# Dashboard_rev7.net
KiCad netlist of a schematic drawn in EAGLE
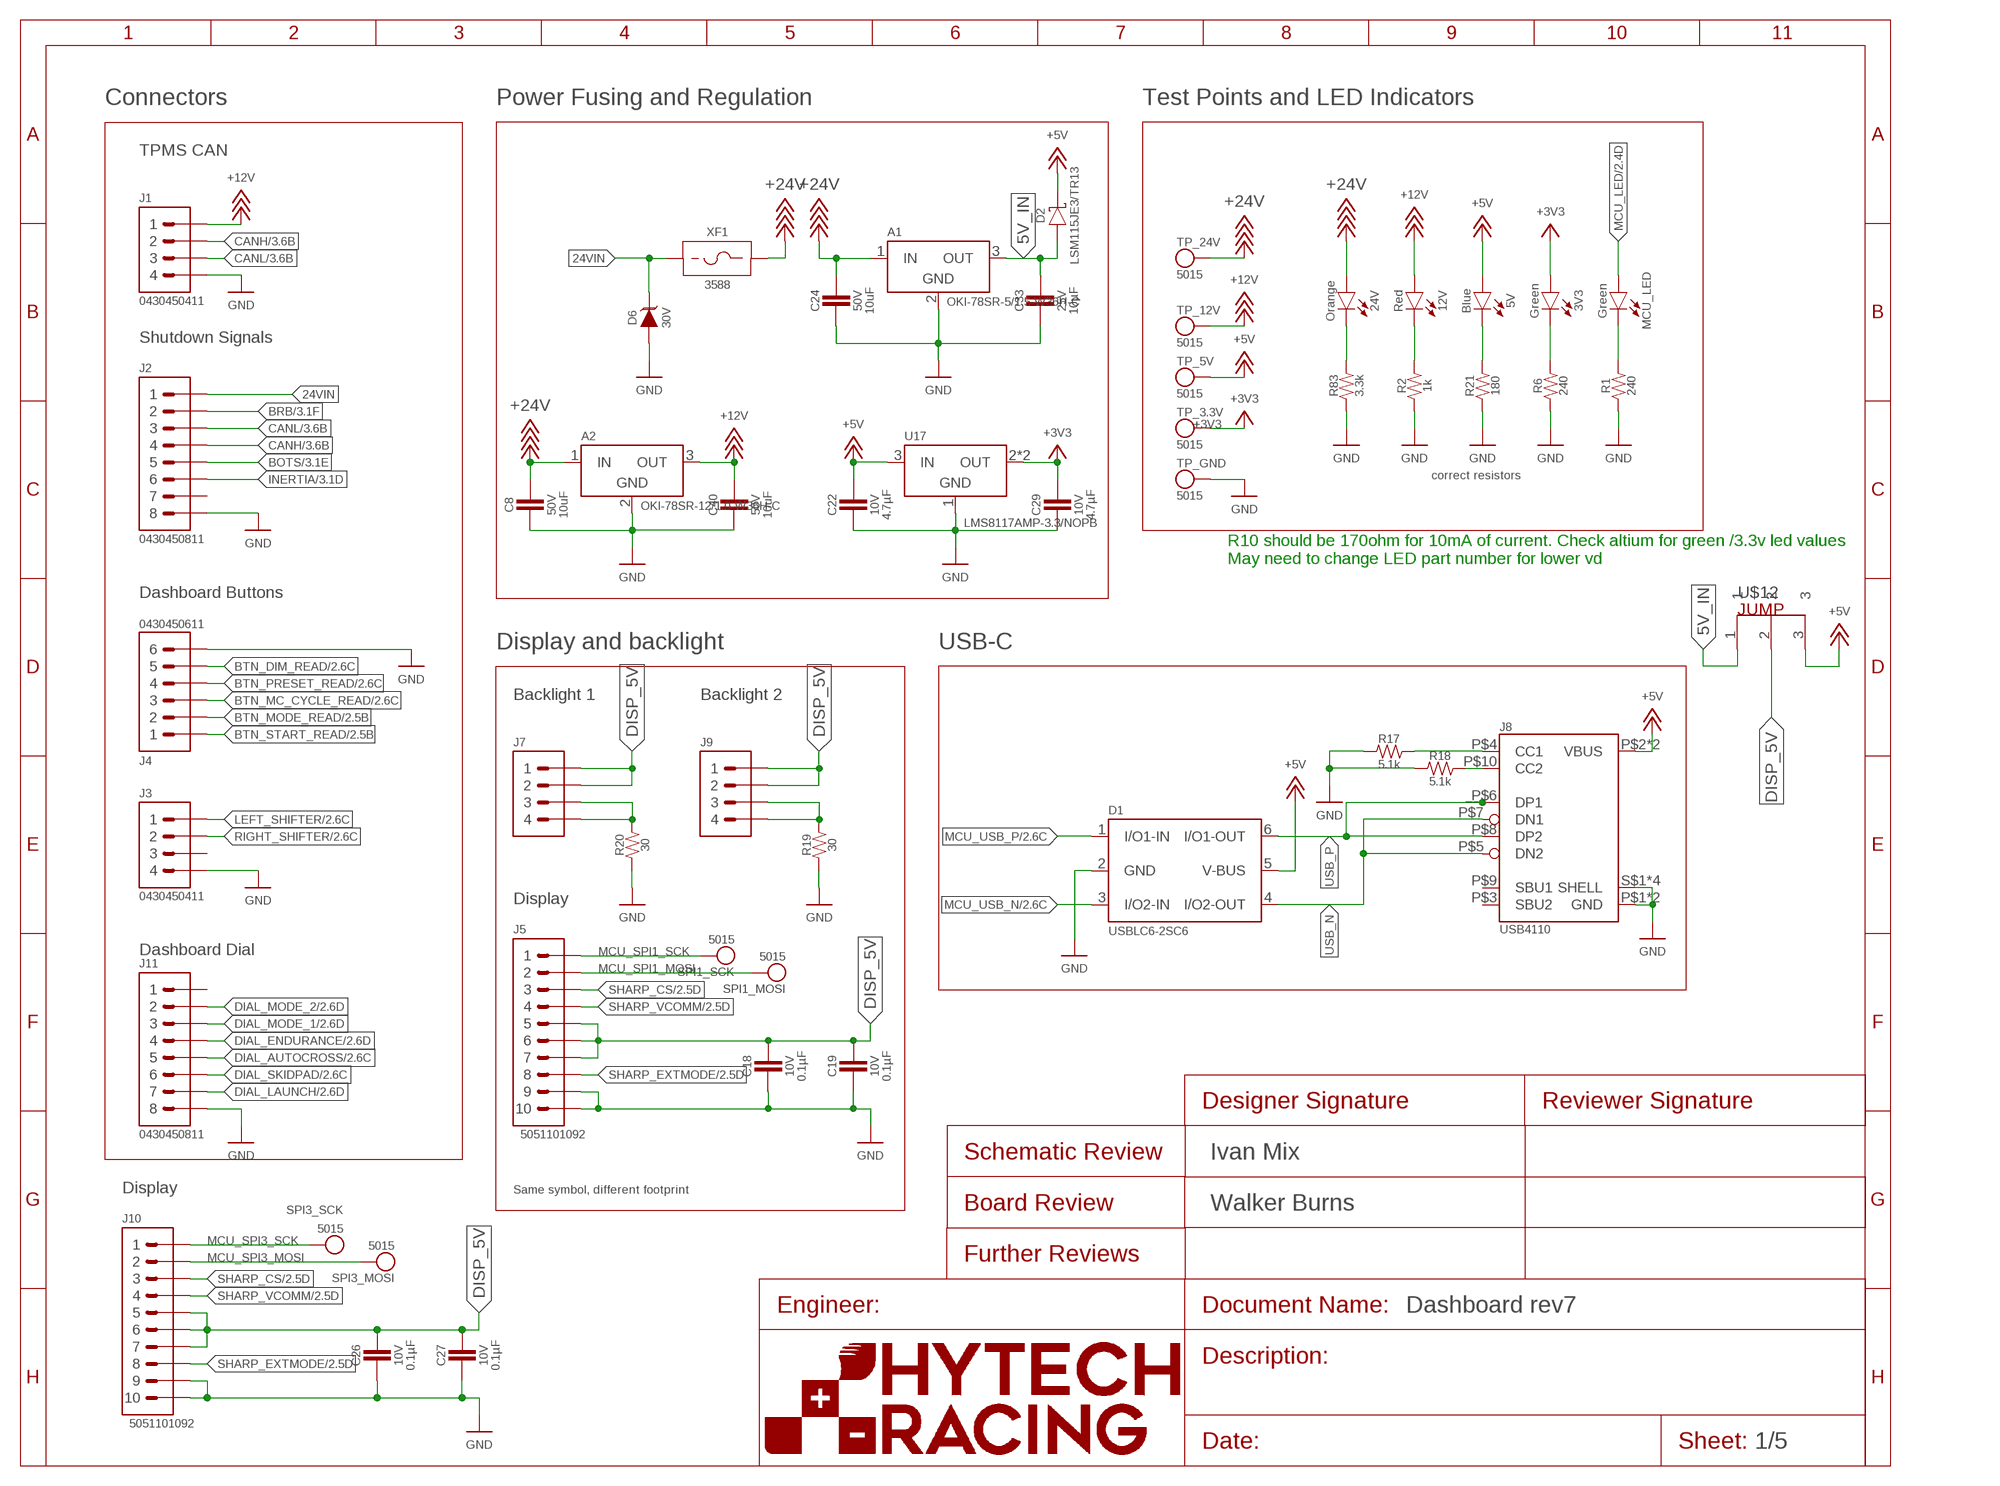
[diagram p0: schematic, sheet 1]
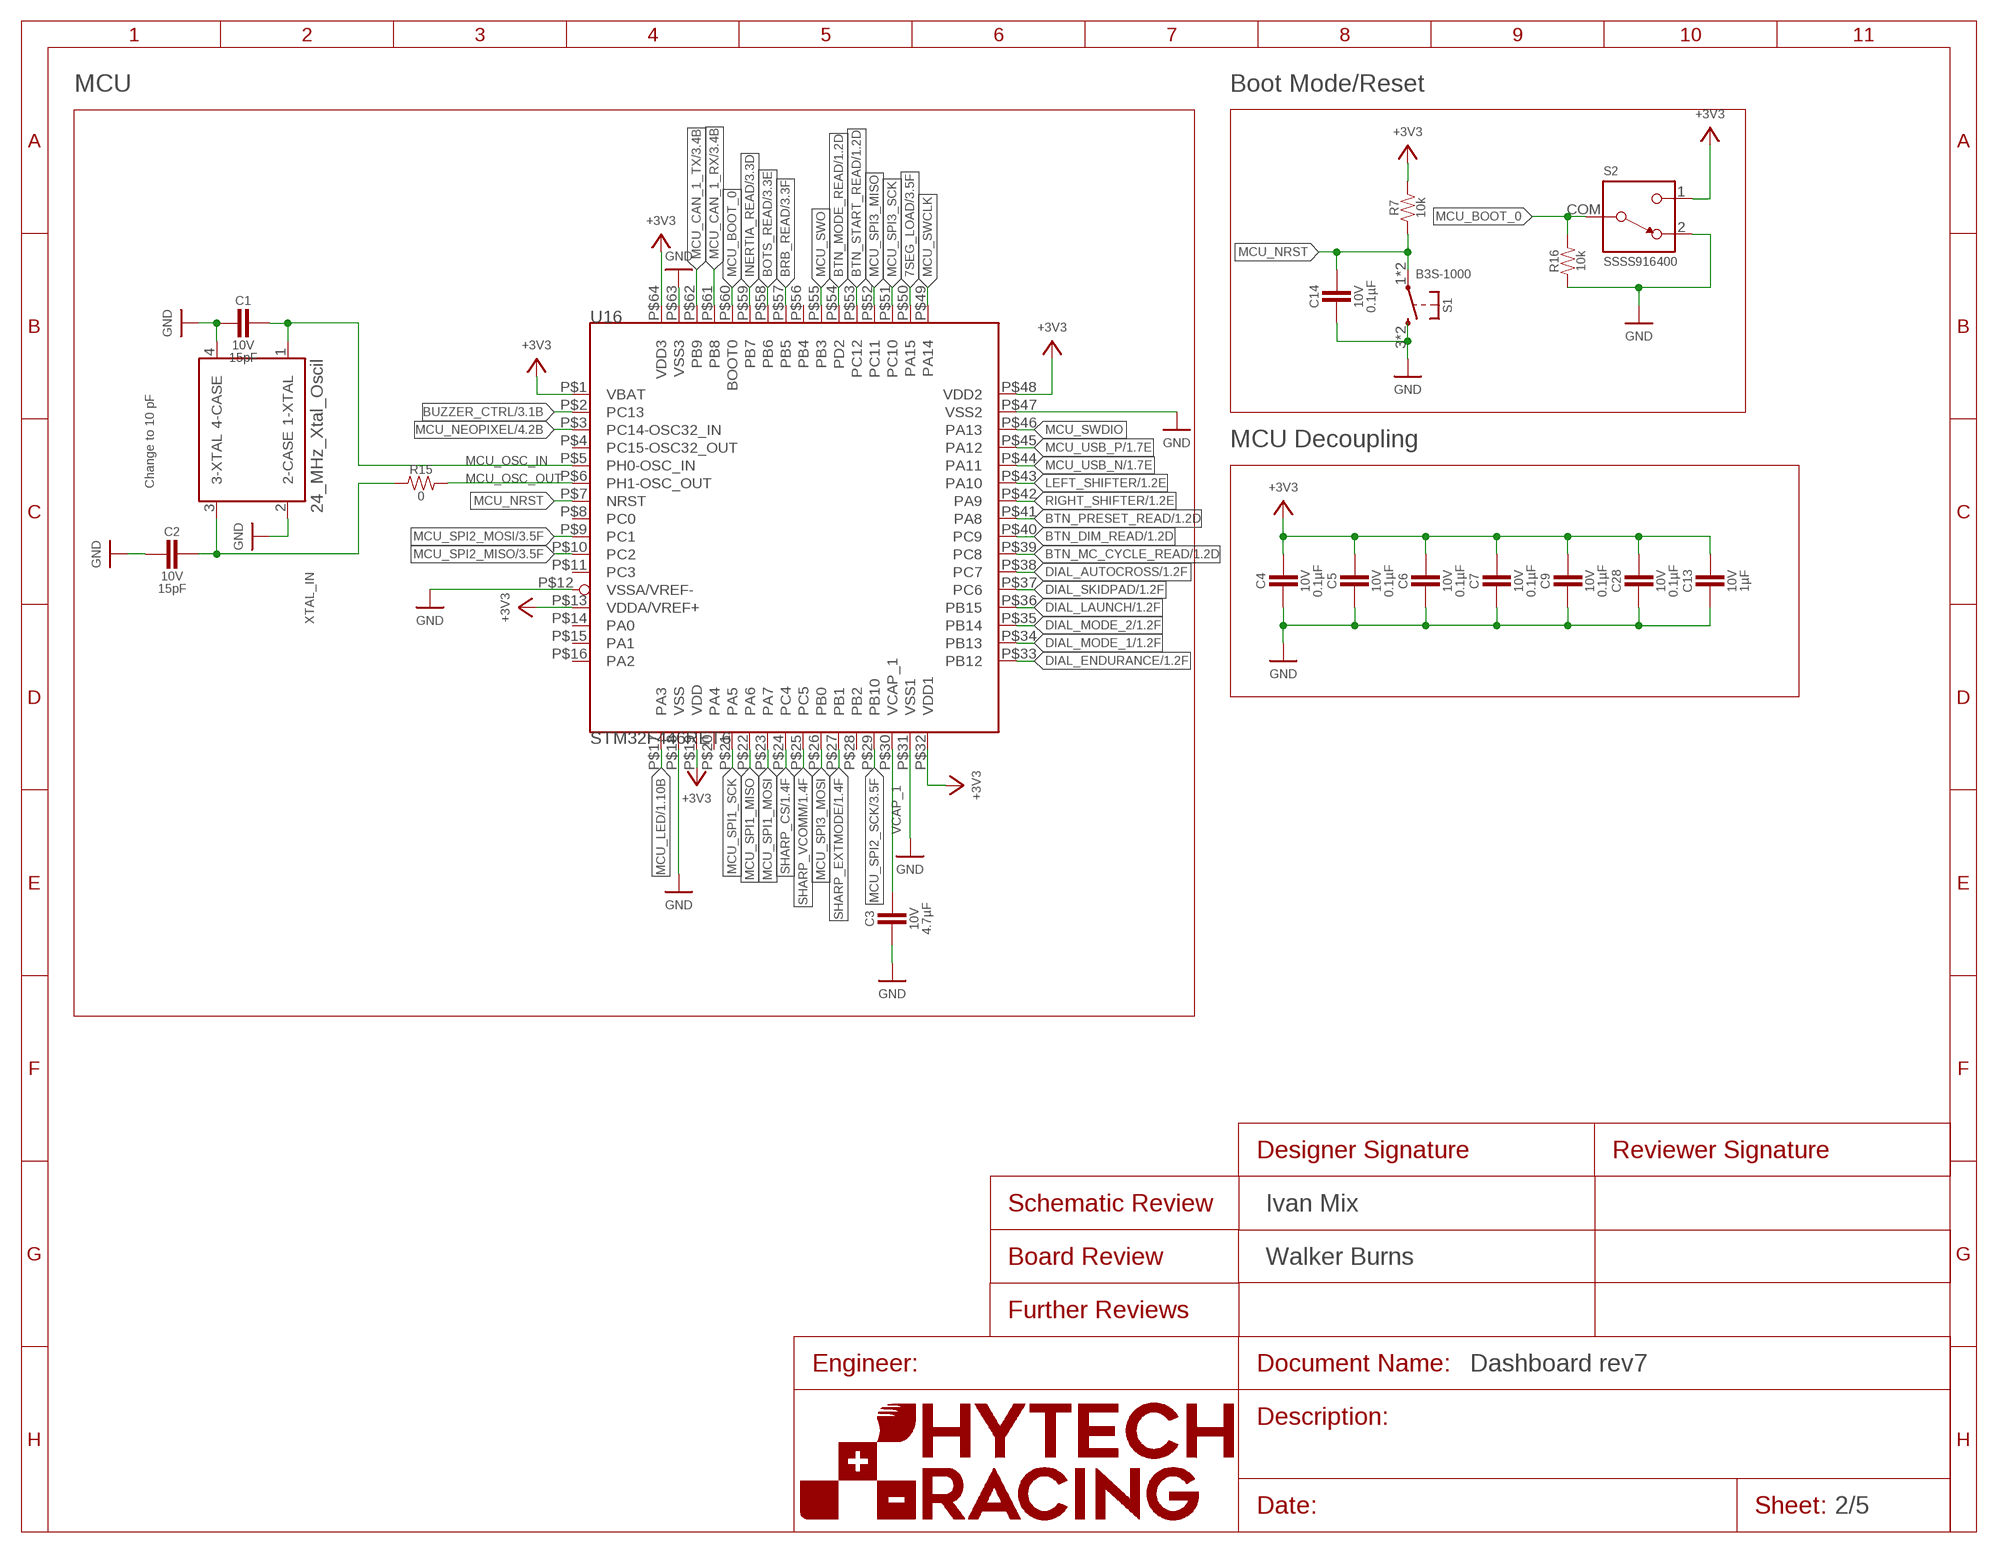
[diagram p1: schematic, sheet 2]
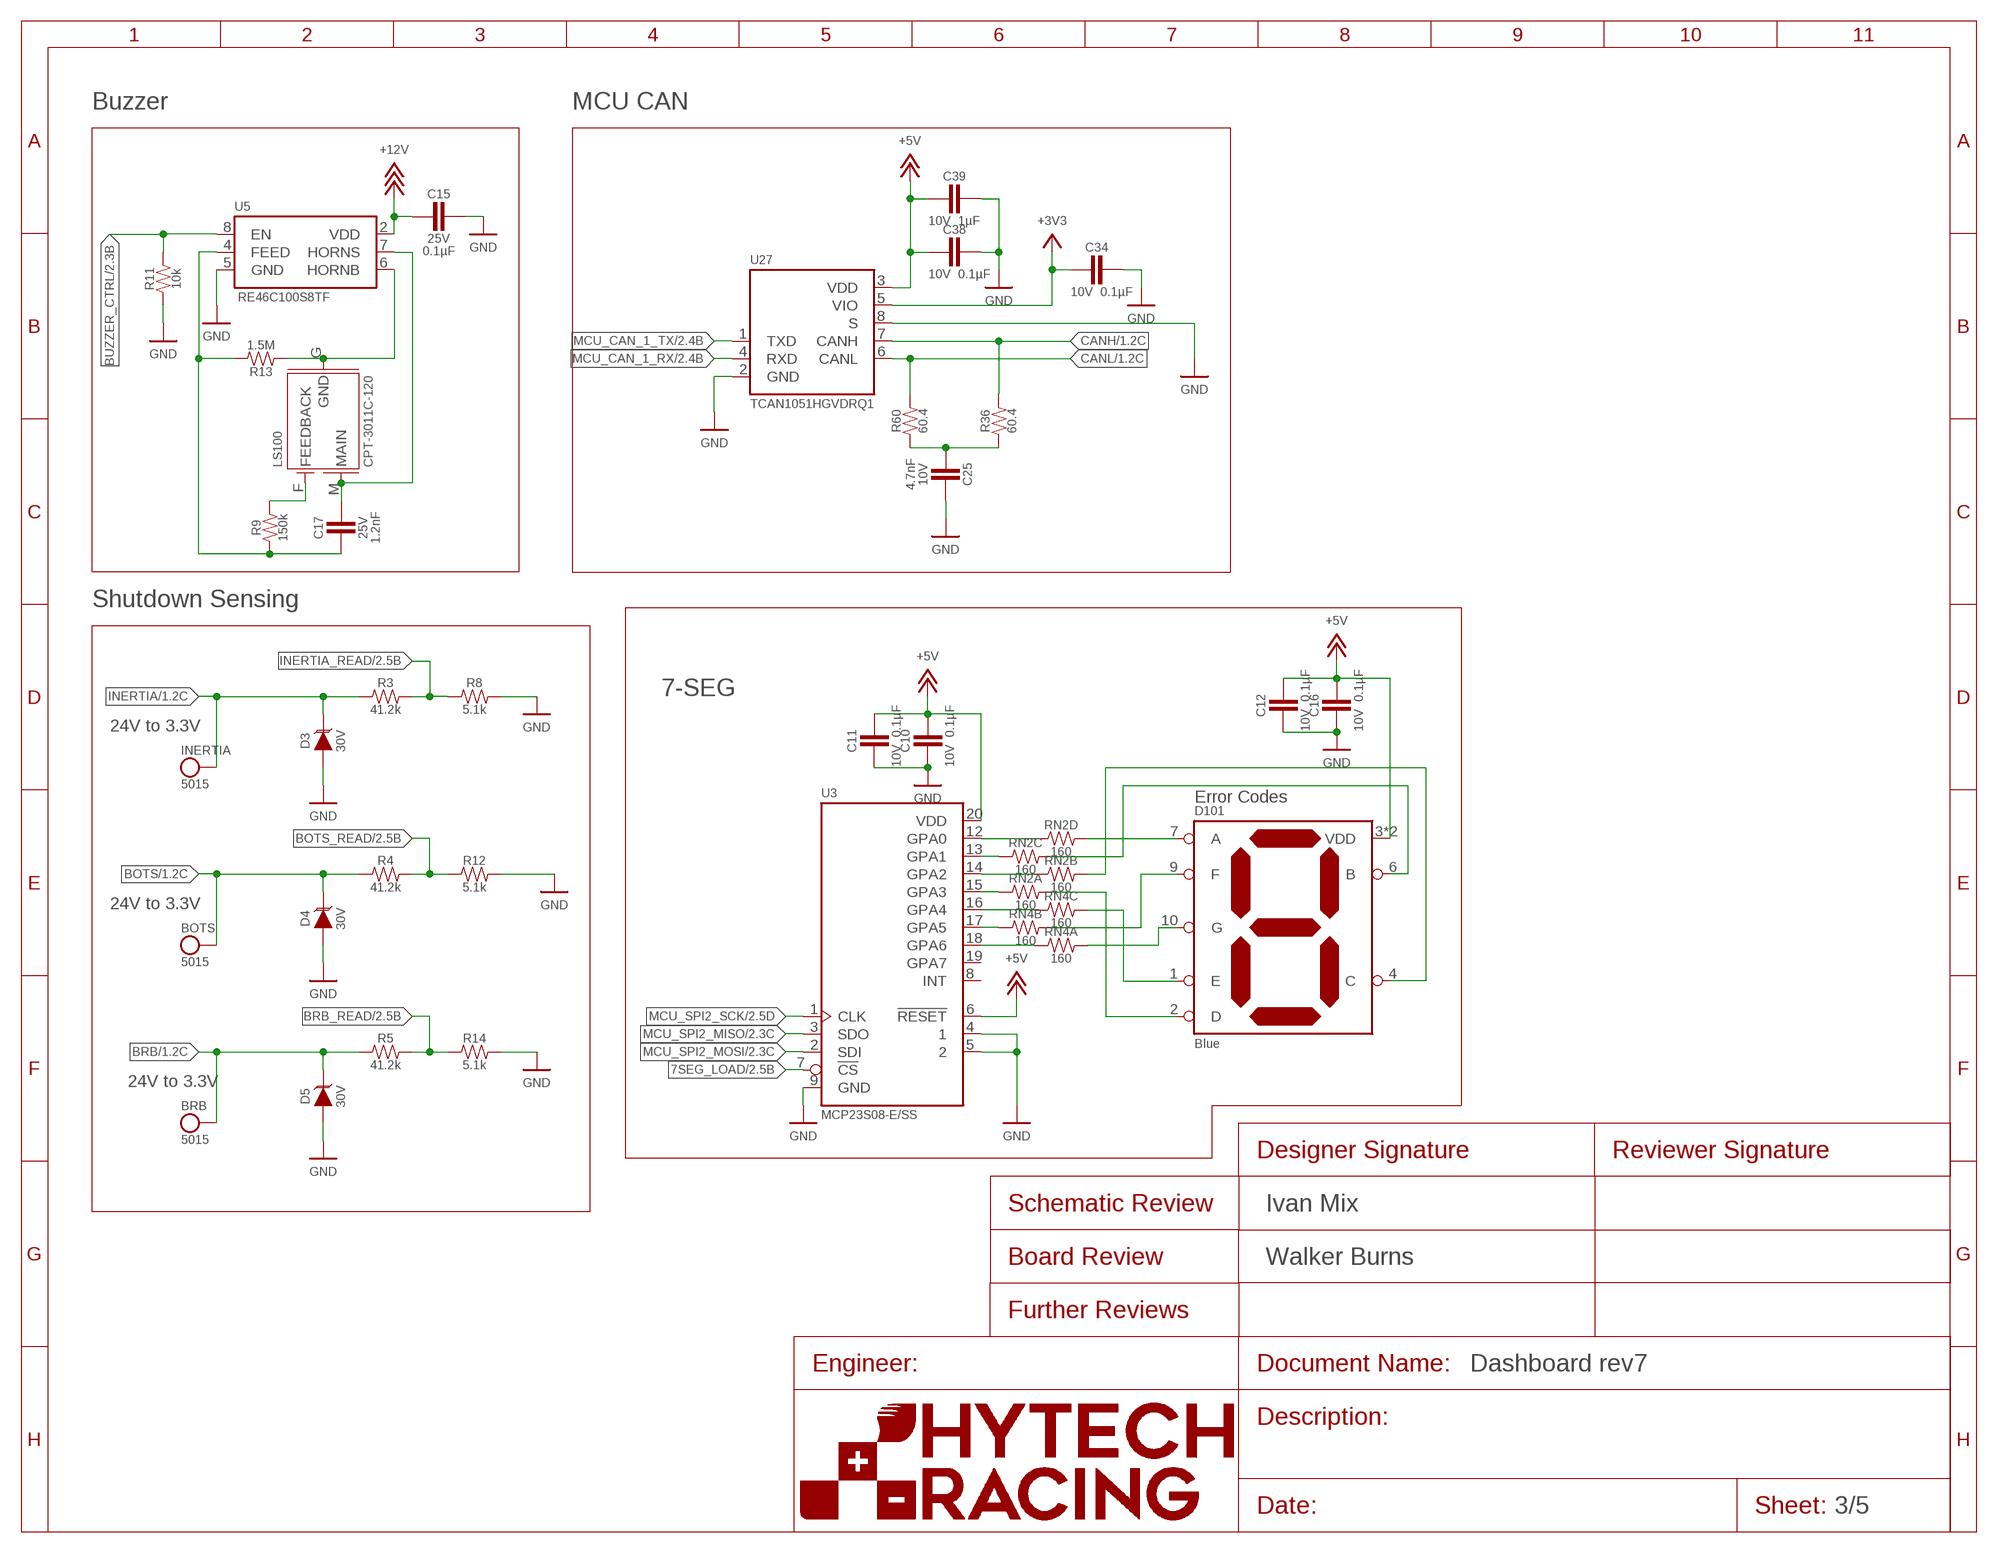
[diagram p2: schematic, sheet 3]
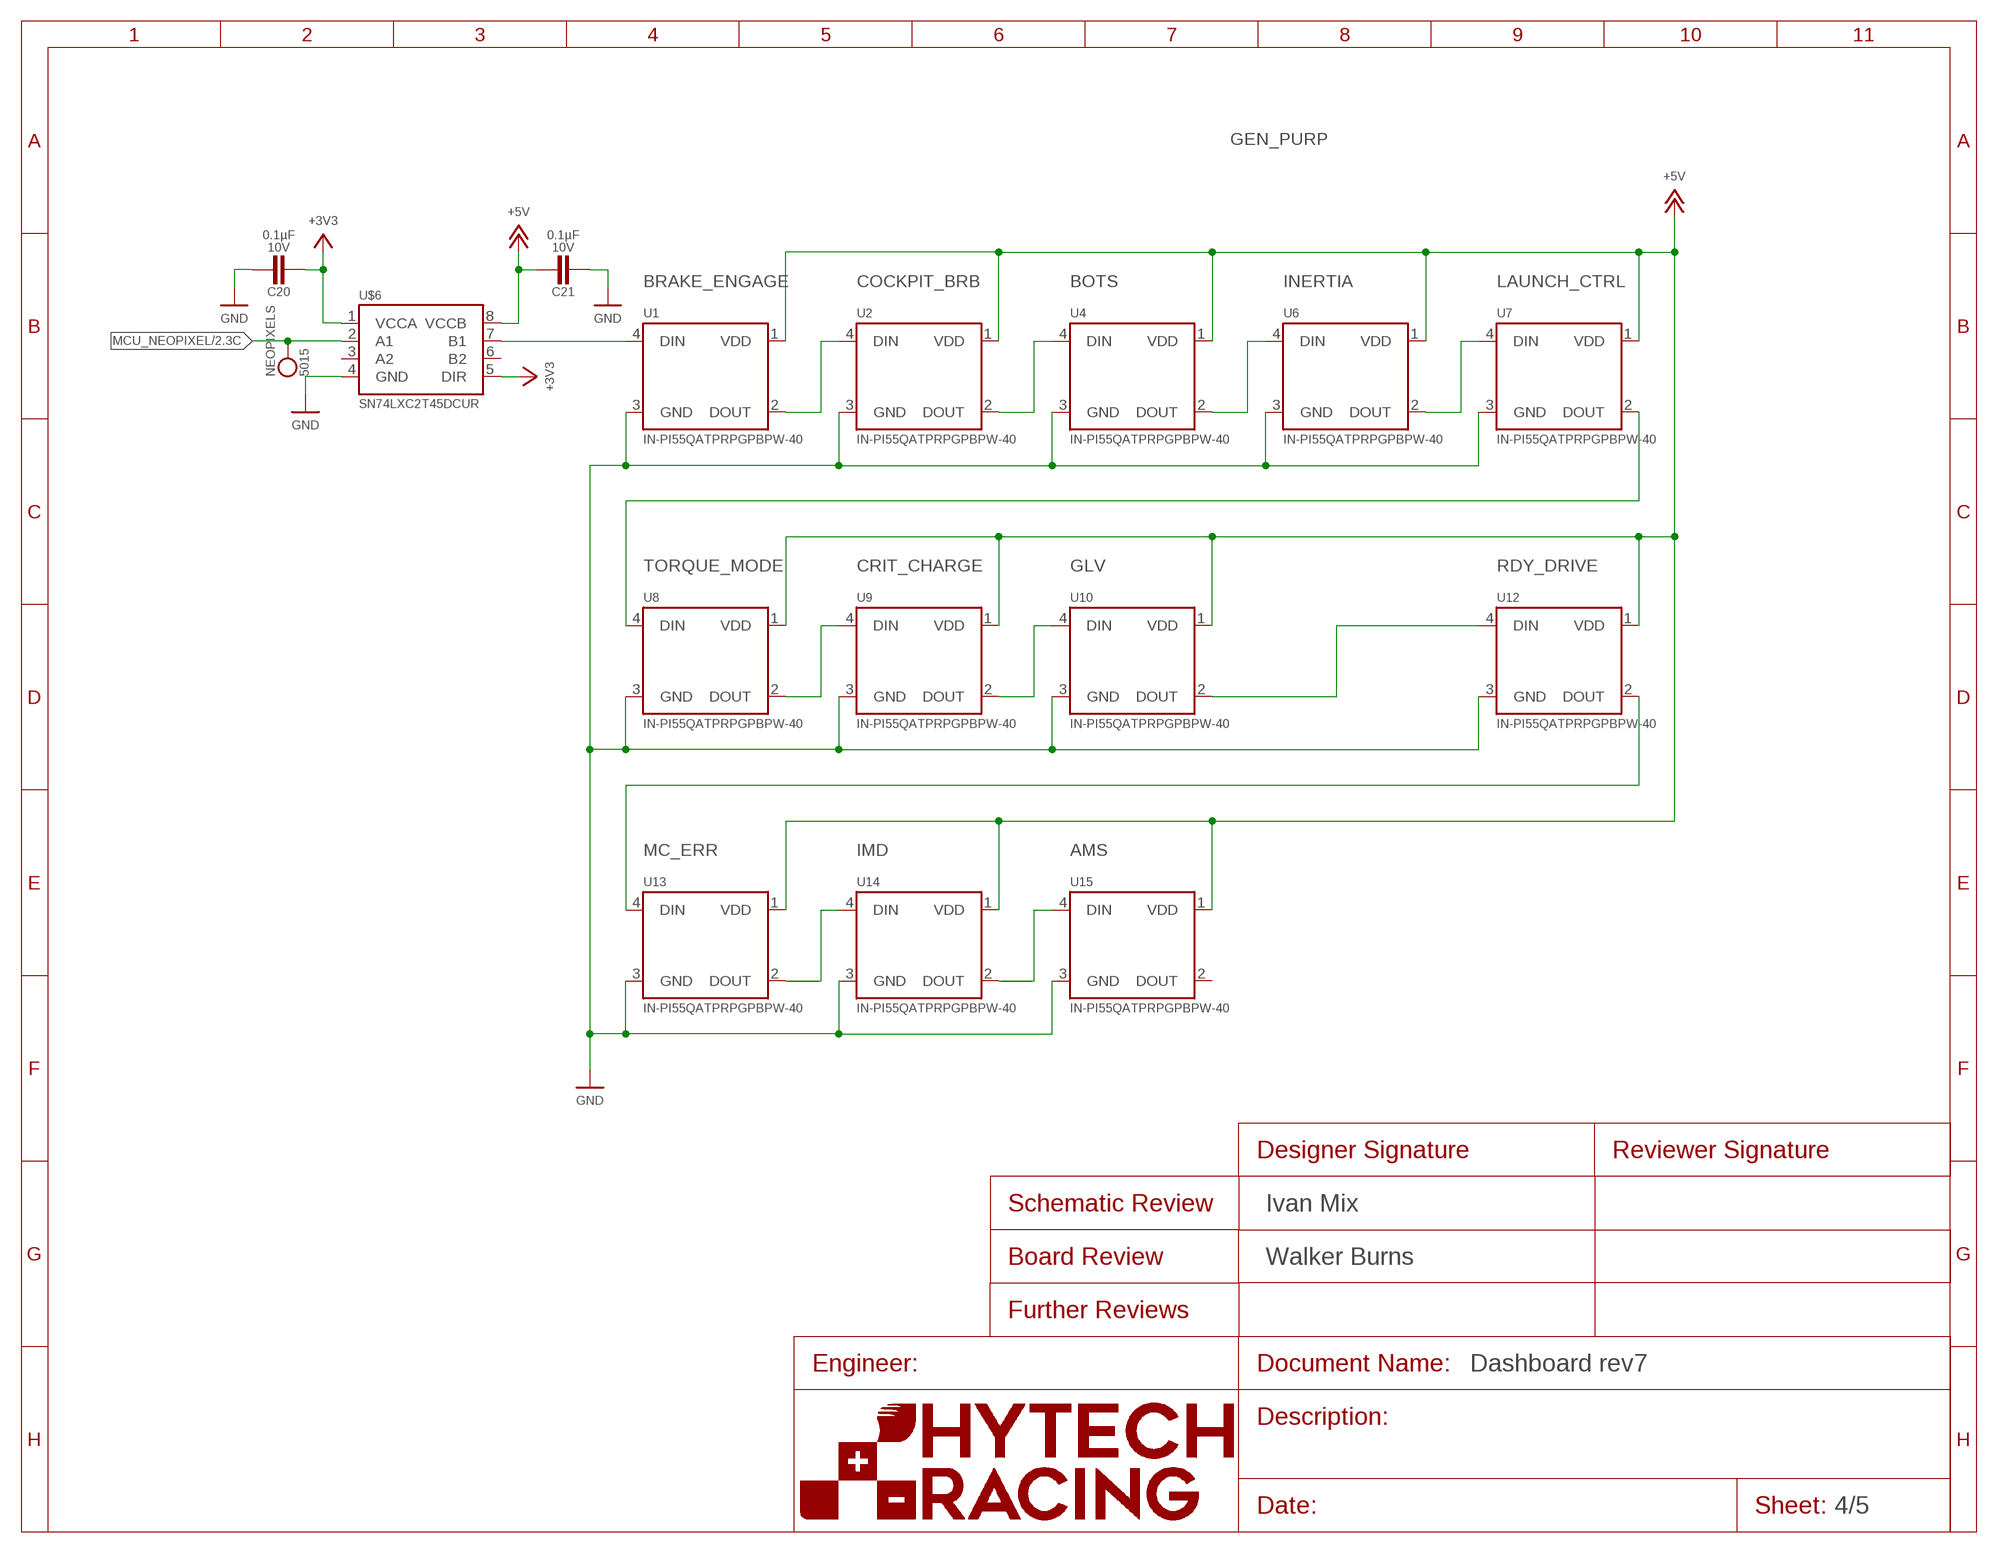
[diagram p3: schematic, sheet 4]
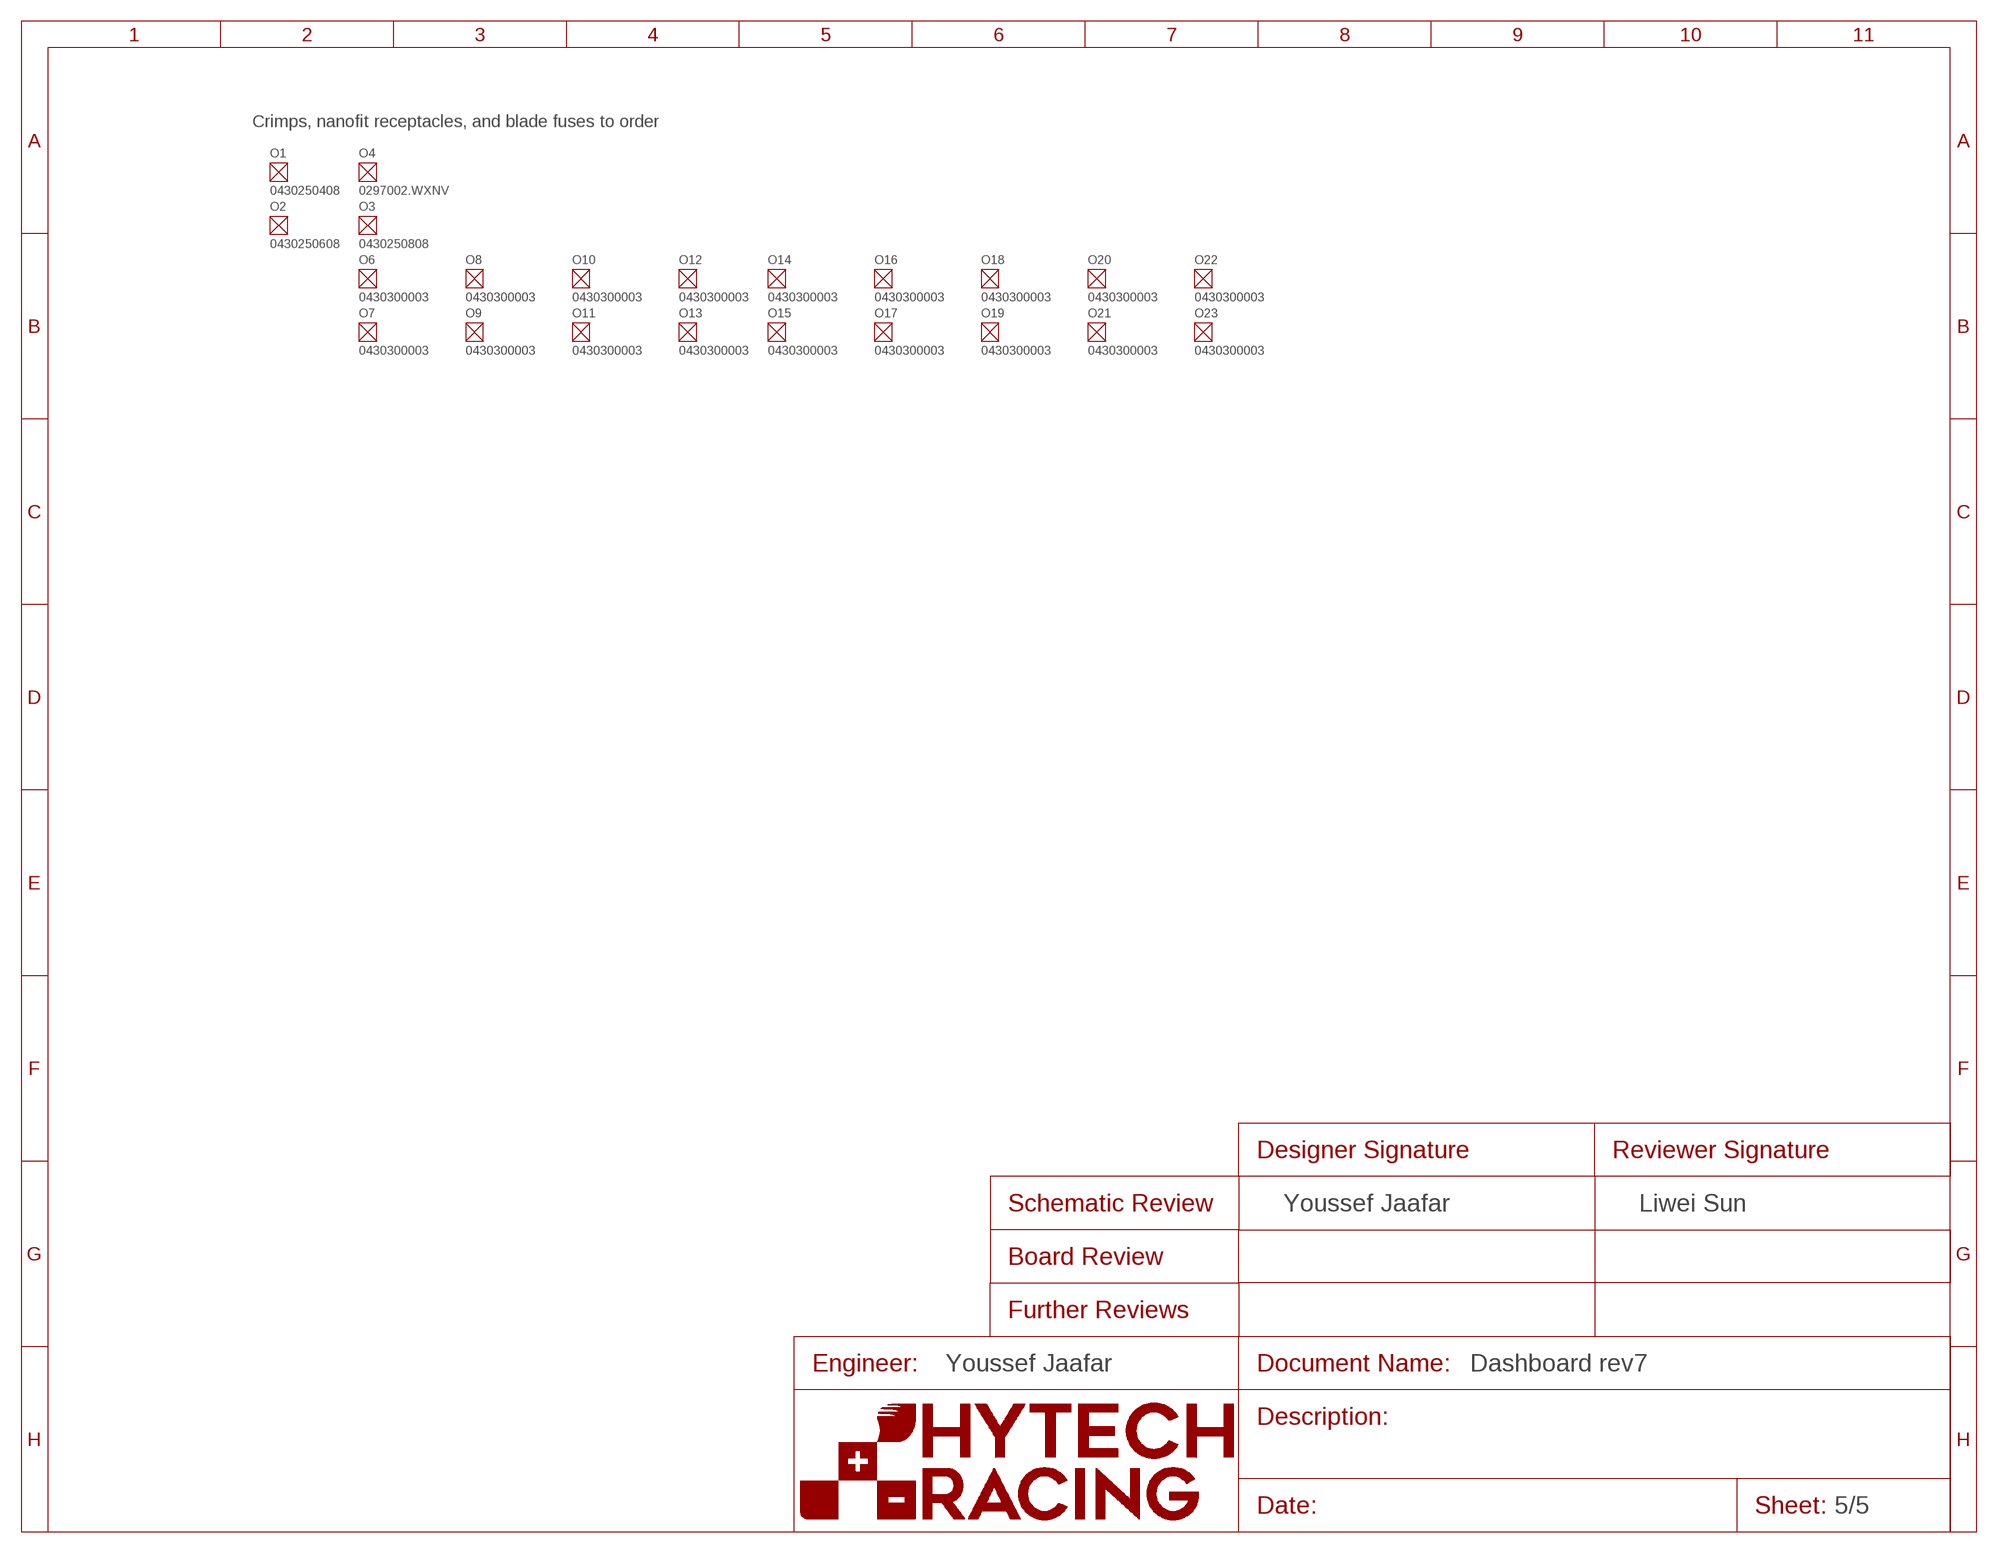
[diagram p4: schematic, sheet 5]

(export (version "E")
  (design (tool "Eeschema 10.0.6"))
  (components
    (comp (ref "C1")
      (value "CAPACITOR_0603_10V_15PF")
      (footprint "eagle-import:0603-CAP")
      (fields
        (field (name "CAPACITANCE") "15pF")
        (field (name "MANUFACTURER") "Vishay Vitramon")
        (field (name "MPN") "VJ0603A150FXQPW1BC")
        (field (name "TOLERANCE") "1%")
        (field (name "VOLTAGE") "10V")
      )
      (libsource (lib "eagle-import") (part "CAPACITOR_?_060310V_15PF"))
    )
    (comp (ref "C2")
      (value "CAPACITOR_0603_10V_15PF")
      (footprint "eagle-import:0603-CAP")
      (fields
        (field (name "CAPACITANCE") "15pF")
        (field (name "MANUFACTURER") "Vishay Vitramon")
        (field (name "MPN") "VJ0603A150FXQPW1BC")
        (field (name "TOLERANCE") "1%")
        (field (name "VOLTAGE") "10V")
      )
      (libsource (lib "eagle-import") (part "CAPACITOR_?_060310V_15PF"))
    )
    (comp (ref "C3")
      (value "CAPACITOR_0603_10V_4.7UF")
      (footprint "eagle-import:0603-CAP")
      (fields
        (field (name "CAPACITANCE") "4.7µF")
        (field (name "MANUFACTURER") "Samsung Electro-Mechanics")
        (field (name "MPN") "CL10A475KP8NNNC")
        (field (name "TOLERANCE") "10%")
        (field (name "VOLTAGE") "10V")
      )
      (libsource (lib "eagle-import") (part "CAPACITOR_?_060310V_4.7UF"))
    )
    (comp (ref "C4")
      (value "CAPACITOR_0603_10V_0.1UF")
      (footprint "eagle-import:0603-CAP")
      (fields
        (field (name "CAPACITANCE") "0.1µF")
        (field (name "MANUFACTURER") "Vishay Vitramon")
        (field (name "MPN") "VJ0603Y104JXQPW1BC")
        (field (name "TOLERANCE") "5%")
        (field (name "VOLTAGE") "10V")
      )
      (libsource (lib "eagle-import") (part "CAPACITOR_?_060310V_0.1UF"))
    )
    (comp (ref "C5")
      (value "CAPACITOR_0603_10V_0.1UF")
      (footprint "eagle-import:0603-CAP")
      (fields
        (field (name "CAPACITANCE") "0.1µF")
        (field (name "MANUFACTURER") "Vishay Vitramon")
        (field (name "MPN") "VJ0603Y104JXQPW1BC")
        (field (name "TOLERANCE") "5%")
        (field (name "VOLTAGE") "10V")
      )
      (libsource (lib "eagle-import") (part "CAPACITOR_?_060310V_0.1UF"))
    )
    (comp (ref "C6")
      (value "CAPACITOR_0603_10V_0.1UF")
      (footprint "eagle-import:0603-CAP")
      (fields
        (field (name "CAPACITANCE") "0.1µF")
        (field (name "MANUFACTURER") "Vishay Vitramon")
        (field (name "MPN") "VJ0603Y104JXQPW1BC")
        (field (name "TOLERANCE") "5%")
        (field (name "VOLTAGE") "10V")
      )
      (libsource (lib "eagle-import") (part "CAPACITOR_?_060310V_0.1UF"))
    )
    (comp (ref "C7")
      (value "CAPACITOR_0603_10V_0.1UF")
      (footprint "eagle-import:0603-CAP")
      (fields
        (field (name "CAPACITANCE") "0.1µF")
        (field (name "MANUFACTURER") "Vishay Vitramon")
        (field (name "MPN") "VJ0603Y104JXQPW1BC")
        (field (name "TOLERANCE") "5%")
        (field (name "VOLTAGE") "10V")
      )
      (libsource (lib "eagle-import") (part "CAPACITOR_?_060310V_0.1UF"))
    )
    (comp (ref "C9")
      (value "CAPACITOR_0603_10V_0.1UF")
      (footprint "eagle-import:0603-CAP")
      (fields
        (field (name "CAPACITANCE") "0.1µF")
        (field (name "MANUFACTURER") "Vishay Vitramon")
        (field (name "MPN") "VJ0603Y104JXQPW1BC")
        (field (name "TOLERANCE") "5%")
        (field (name "VOLTAGE") "10V")
      )
      (libsource (lib "eagle-import") (part "CAPACITOR_?_060310V_0.1UF"))
    )
    (comp (ref "C13")
      (value "CAPACITOR_0603_10V_1UF")
      (footprint "eagle-import:0603-CAP")
      (fields
        (field (name "CAPACITANCE") "1µF")
        (field (name "MANUFACTURER") "Yageo")
        (field (name "MPN") "CC0603KRX7R6BB105")
        (field (name "TOLERANCE") "10%")
        (field (name "VOLTAGE") "10V")
      )
      (libsource (lib "eagle-import") (part "CAPACITOR_?_060310V_1UF"))
    )
    (comp (ref "C14")
      (value "CAPACITOR_0603_10V_0.1UF")
      (footprint "eagle-import:0603-CAP")
      (fields
        (field (name "CAPACITANCE") "0.1µF")
        (field (name "MANUFACTURER") "Vishay Vitramon")
        (field (name "MPN") "VJ0603Y104JXQPW1BC")
        (field (name "TOLERANCE") "5%")
        (field (name "VOLTAGE") "10V")
      )
      (libsource (lib "eagle-import") (part "CAPACITOR_?_060310V_0.1UF"))
    )
    (comp (ref "C28")
      (value "CAPACITOR_0603_10V_0.1UF")
      (footprint "eagle-import:0603-CAP")
      (fields
        (field (name "CAPACITANCE") "0.1µF")
        (field (name "MANUFACTURER") "Vishay Vitramon")
        (field (name "MPN") "VJ0603Y104JXQPW1BC")
        (field (name "TOLERANCE") "5%")
        (field (name "VOLTAGE") "10V")
      )
      (libsource (lib "eagle-import") (part "CAPACITOR_?_060310V_0.1UF"))
    )
    (comp (ref "R7")
      (value "RESISTOR_0603_10K")
      (footprint "eagle-import:0603-RES")
      (fields
        (field (name "MANUFACTURER") "Panasonic Electronic Components")
        (field (name "MPN") "ERA-3ARB103V")
        (field (name "POWER") "0.1W")
        (field (name "RESISTANCE") "10k")
      )
      (libsource (lib "eagle-import") (part "RESISTOR_?_060310K"))
    )
    (comp (ref "R15")
      (value "RESISTOR_0603_0")
      (footprint "eagle-import:0603-RES")
      (fields
        (field (name "MANUFACTURER") "Yageo")
        (field (name "MPN") "RC0603FR-070RL")
        (field (name "POWER") "0.1W")
        (field (name "RESISTANCE") "0")
      )
      (libsource (lib "eagle-import") (part "RESISTOR_?_06030"))
    )
    (comp (ref "R16")
      (value "RESISTOR_0603_10K")
      (footprint "eagle-import:0603-RES")
      (fields
        (field (name "MANUFACTURER") "Panasonic Electronic Components")
        (field (name "MPN") "ERA-3ARB103V")
        (field (name "POWER") "0.1W")
        (field (name "RESISTANCE") "10k")
      )
      (libsource (lib "eagle-import") (part "RESISTOR_?_060310K"))
    )
    (comp (ref "S1")
      (value "BUTTON")
      (footprint "eagle-import:B3S-100X")
      (fields (field (name "MPN") "B3S-1000") (field (name "MANUFACTURER") "Omron"))
      (libsource (lib "eagle-import") (part "BUTTON"))
    )
    (comp (ref "S2")
      (value "SWITCH_SPDT_SSSS916400")
      (footprint "eagle-import:SSSS916400")
      (fields (field (name "MPN") "SSSS916400") (field (name "MANUFACTURER") "Alps Alpine"))
      (libsource (lib "eagle-import") (part "SWITCH_SPDT_SSSS916400"))
    )
    (comp (ref "U16")
      (value "STM32-LQFP64")
      (footprint "eagle-import:STM32-FOOTPRINT")
      (fields (field (name "MPN") "STM32F446RET6") (field (name "MANUFACTURER") "STMicroelectronics"))
      (libsource (lib "eagle-import") (part "STM32-LQFP64"))
    )
    (comp (ref "X1")
      (value "24_MHZ_XTAL_OSCILLATOR")
      (footprint "eagle-import:24_MHZ_XTAL_OSCILLATOR")
      (fields (field (name "MPN") "FL2400022"))
      (libsource (lib "eagle-import") (part "24_MHZ_XTAL_OSCILLATOR"))
    )
    (comp (ref "C20")
      (value "CAPACITOR_0603_10V_0.1UF")
      (footprint "eagle-import:0603-CAP")
      (fields
        (field (name "CAPACITANCE") "0.1µF")
        (field (name "MANUFACTURER") "Vishay Vitramon")
        (field (name "MPN") "VJ0603Y104JXQPW1BC")
        (field (name "TOLERANCE") "5%")
        (field (name "VOLTAGE") "10V")
      )
      (libsource (lib "eagle-import") (part "CAPACITOR_?_060310V_0.1UF"))
    )
    (comp (ref "C21")
      (value "CAPACITOR_0603_10V_0.1UF")
      (footprint "eagle-import:0603-CAP")
      (fields
        (field (name "CAPACITANCE") "0.1µF")
        (field (name "MANUFACTURER") "Vishay Vitramon")
        (field (name "MPN") "VJ0603Y104JXQPW1BC")
        (field (name "TOLERANCE") "5%")
        (field (name "VOLTAGE") "10V")
      )
      (libsource (lib "eagle-import") (part "CAPACITOR_?_060310V_0.1UF"))
    )
    (comp (ref "NEOPIXELS")
      (value "TEST_POINT")
      (footprint "eagle-import:5015")
      (fields (field (name "MPN") "5015") (field (name "MANUFACTURER") "Keystone Electronics"))
      (libsource (lib "eagle-import") (part "TEST_POINT"))
    )
    (comp (ref "U$6")
      (value "SN74LXC2T45DCUR")
      (footprint "eagle-import:8-VSSOP")
      (fields (field (name "MPN") "SN74LXC2T45DCUR") (field (name "MANUFACTURER") "Texas Instruments"))
      (libsource (lib "eagle-import") (part "SN74LXC2T45DCUR"))
    )
    (comp (ref "U1")
      (value "NEOPIXEL_IN-PI55QATPRPGPBPW-40")
      (footprint "eagle-import:NEOPIXEL")
      (fields (field (name "MPN") "IN-PI55QATPRPGPBPW-40") (field (name "MANUFACTURER") "Inolux"))
      (libsource (lib "eagle-import") (part "NEOPIXEL_IN-PI55QATPRPGPBPW-40"))
    )
    (comp (ref "U2")
      (value "NEOPIXEL_IN-PI55QATPRPGPBPW-40")
      (footprint "eagle-import:NEOPIXEL")
      (fields (field (name "MPN") "IN-PI55QATPRPGPBPW-40") (field (name "MANUFACTURER") "Inolux"))
      (libsource (lib "eagle-import") (part "NEOPIXEL_IN-PI55QATPRPGPBPW-40"))
    )
    (comp (ref "U4")
      (value "NEOPIXEL_IN-PI55QATPRPGPBPW-40")
      (footprint "eagle-import:NEOPIXEL")
      (fields (field (name "MPN") "IN-PI55QATPRPGPBPW-40") (field (name "MANUFACTURER") "Inolux"))
      (libsource (lib "eagle-import") (part "NEOPIXEL_IN-PI55QATPRPGPBPW-40"))
    )
    (comp (ref "U6")
      (value "NEOPIXEL_IN-PI55QATPRPGPBPW-40")
      (footprint "eagle-import:NEOPIXEL")
      (fields (field (name "MPN") "IN-PI55QATPRPGPBPW-40") (field (name "MANUFACTURER") "Inolux"))
      (libsource (lib "eagle-import") (part "NEOPIXEL_IN-PI55QATPRPGPBPW-40"))
    )
    (comp (ref "U7")
      (value "NEOPIXEL_IN-PI55QATPRPGPBPW-40")
      (footprint "eagle-import:NEOPIXEL")
      (fields (field (name "MPN") "IN-PI55QATPRPGPBPW-40") (field (name "MANUFACTURER") "Inolux"))
      (libsource (lib "eagle-import") (part "NEOPIXEL_IN-PI55QATPRPGPBPW-40"))
    )
    (comp (ref "U8")
      (value "NEOPIXEL_IN-PI55QATPRPGPBPW-40")
      (footprint "eagle-import:NEOPIXEL")
      (fields (field (name "MPN") "IN-PI55QATPRPGPBPW-40") (field (name "MANUFACTURER") "Inolux"))
      (libsource (lib "eagle-import") (part "NEOPIXEL_IN-PI55QATPRPGPBPW-40"))
    )
    (comp (ref "U9")
      (value "NEOPIXEL_IN-PI55QATPRPGPBPW-40")
      (footprint "eagle-import:NEOPIXEL")
      (fields (field (name "MPN") "IN-PI55QATPRPGPBPW-40") (field (name "MANUFACTURER") "Inolux"))
      (libsource (lib "eagle-import") (part "NEOPIXEL_IN-PI55QATPRPGPBPW-40"))
    )
    (comp (ref "U10")
      (value "NEOPIXEL_IN-PI55QATPRPGPBPW-40")
      (footprint "eagle-import:NEOPIXEL")
      (fields (field (name "MPN") "IN-PI55QATPRPGPBPW-40") (field (name "MANUFACTURER") "Inolux"))
      (libsource (lib "eagle-import") (part "NEOPIXEL_IN-PI55QATPRPGPBPW-40"))
    )
    (comp (ref "U12")
      (value "NEOPIXEL_IN-PI55QATPRPGPBPW-40")
      (footprint "eagle-import:NEOPIXEL")
      (fields (field (name "MPN") "IN-PI55QATPRPGPBPW-40") (field (name "MANUFACTURER") "Inolux"))
      (libsource (lib "eagle-import") (part "NEOPIXEL_IN-PI55QATPRPGPBPW-40"))
    )
    (comp (ref "U13")
      (value "NEOPIXEL_IN-PI55QATPRPGPBPW-40")
      (footprint "eagle-import:NEOPIXEL")
      (fields (field (name "MPN") "IN-PI55QATPRPGPBPW-40") (field (name "MANUFACTURER") "Inolux"))
      (libsource (lib "eagle-import") (part "NEOPIXEL_IN-PI55QATPRPGPBPW-40"))
    )
    (comp (ref "U14")
      (value "NEOPIXEL_IN-PI55QATPRPGPBPW-40")
      (footprint "eagle-import:NEOPIXEL")
      (fields (field (name "MPN") "IN-PI55QATPRPGPBPW-40") (field (name "MANUFACTURER") "Inolux"))
      (libsource (lib "eagle-import") (part "NEOPIXEL_IN-PI55QATPRPGPBPW-40"))
    )
    (comp (ref "U15")
      (value "NEOPIXEL_IN-PI55QATPRPGPBPW-40")
      (footprint "eagle-import:NEOPIXEL")
      (fields (field (name "MPN") "IN-PI55QATPRPGPBPW-40") (field (name "MANUFACTURER") "Inolux"))
      (libsource (lib "eagle-import") (part "NEOPIXEL_IN-PI55QATPRPGPBPW-40"))
    )
    (comp (ref "BOTS")
      (value "TEST_POINT")
      (footprint "eagle-import:5015")
      (fields (field (name "MPN") "5015") (field (name "MANUFACTURER") "Keystone Electronics"))
      (libsource (lib "eagle-import") (part "TEST_POINT"))
    )
    (comp (ref "BRB")
      (value "TEST_POINT")
      (footprint "eagle-import:5015")
      (fields (field (name "MPN") "5015") (field (name "MANUFACTURER") "Keystone Electronics"))
      (libsource (lib "eagle-import") (part "TEST_POINT"))
    )
    (comp (ref "C10")
      (value "CAPACITOR_0603_10V_0.1UF")
      (footprint "eagle-import:0603-CAP")
      (fields
        (field (name "CAPACITANCE") "0.1µF")
        (field (name "MANUFACTURER") "Vishay Vitramon")
        (field (name "MPN") "VJ0603Y104JXQPW1BC")
        (field (name "TOLERANCE") "5%")
        (field (name "VOLTAGE") "10V")
      )
      (libsource (lib "eagle-import") (part "CAPACITOR_?_060310V_0.1UF"))
    )
    (comp (ref "C11")
      (value "CAPACITOR_0603_10V_0.1UF")
      (footprint "eagle-import:0603-CAP")
      (fields
        (field (name "CAPACITANCE") "0.1µF")
        (field (name "MANUFACTURER") "Vishay Vitramon")
        (field (name "MPN") "VJ0603Y104JXQPW1BC")
        (field (name "TOLERANCE") "5%")
        (field (name "VOLTAGE") "10V")
      )
      (libsource (lib "eagle-import") (part "CAPACITOR_?_060310V_0.1UF"))
    )
    (comp (ref "C12")
      (value "CAPACITOR_0603_10V_0.1UF")
      (footprint "eagle-import:0603-CAP")
      (fields
        (field (name "CAPACITANCE") "0.1µF")
        (field (name "MANUFACTURER") "Vishay Vitramon")
        (field (name "MPN") "VJ0603Y104JXQPW1BC")
        (field (name "TOLERANCE") "5%")
        (field (name "VOLTAGE") "10V")
      )
      (libsource (lib "eagle-import") (part "CAPACITOR_?_060310V_0.1UF"))
    )
    (comp (ref "C15")
      (value "CAPACITOR_0603_25V_0.1UF")
      (footprint "eagle-import:0603-CAP")
      (fields
        (field (name "CAPACITANCE") "0.1µF")
        (field (name "MANUFACTURER") "Samsung Electro-Mechanics")
        (field (name "MPN") "CL10B104KA8NNNC")
        (field (name "TOLERANCE") "10%")
        (field (name "VOLTAGE") "25V")
      )
      (libsource (lib "eagle-import") (part "CAPACITOR_?_060325V_0.1UF"))
    )
    (comp (ref "C16")
      (value "CAPACITOR_0603_10V_0.1UF")
      (footprint "eagle-import:0603-CAP")
      (fields
        (field (name "CAPACITANCE") "0.1µF")
        (field (name "MANUFACTURER") "Vishay Vitramon")
        (field (name "MPN") "VJ0603Y104JXQPW1BC")
        (field (name "TOLERANCE") "5%")
        (field (name "VOLTAGE") "10V")
      )
      (libsource (lib "eagle-import") (part "CAPACITOR_?_060310V_0.1UF"))
    )
    (comp (ref "C17")
      (value "CAPACITOR_0603_25V_1.2NF")
      (footprint "eagle-import:0603-CAP")
      (fields
        (field (name "CAPACITANCE") "1.2nF")
        (field (name "MANUFACTURER") "YAGEO")
        (field (name "MPN") "CC0603KRX7R8BB122")
        (field (name "TOLERANCE") "10%")
        (field (name "VOLTAGE") "25V")
      )
      (libsource (lib "eagle-import") (part "CAPACITOR_?_060325V_1.2NF"))
    )
    (comp (ref "C25")
      (value "CAPACITOR_0603_10V_4.7NF")
      (footprint "eagle-import:0603-CAP")
      (fields
        (field (name "CAPACITANCE") "4.7nF")
        (field (name "MANUFACTURER") "Würth Elektronik")
        (field (name "MPN") "885012206012")
        (field (name "TOLERANCE") "10%")
        (field (name "VOLTAGE") "10V")
      )
      (libsource (lib "eagle-import") (part "CAPACITOR_?_060310V_4.7NF"))
    )
    (comp (ref "C34")
      (value "CAPACITOR_0603_10V_0.1UF")
      (footprint "eagle-import:0603-CAP")
      (fields
        (field (name "CAPACITANCE") "0.1µF")
        (field (name "MANUFACTURER") "Vishay Vitramon")
        (field (name "MPN") "VJ0603Y104JXQPW1BC")
        (field (name "TOLERANCE") "5%")
        (field (name "VOLTAGE") "10V")
      )
      (libsource (lib "eagle-import") (part "CAPACITOR_?_060310V_0.1UF"))
    )
    (comp (ref "C38")
      (value "CAPACITOR_0603_10V_0.1UF")
      (footprint "eagle-import:0603-CAP")
      (fields
        (field (name "CAPACITANCE") "0.1µF")
        (field (name "MANUFACTURER") "Vishay Vitramon")
        (field (name "MPN") "VJ0603Y104JXQPW1BC")
        (field (name "TOLERANCE") "5%")
        (field (name "VOLTAGE") "10V")
      )
      (libsource (lib "eagle-import") (part "CAPACITOR_?_060310V_0.1UF"))
    )
    (comp (ref "C39")
      (value "CAPACITOR_0603_10V_1UF")
      (footprint "eagle-import:0603-CAP")
      (fields
        (field (name "CAPACITANCE") "1µF")
        (field (name "MANUFACTURER") "Yageo")
        (field (name "MPN") "CC0603KRX7R6BB105")
        (field (name "TOLERANCE") "10%")
        (field (name "VOLTAGE") "10V")
      )
      (libsource (lib "eagle-import") (part "CAPACITOR_?_060310V_1UF"))
    )
    (comp (ref "D3")
      (value "TVS_DO-214AA_30V")
      (footprint "eagle-import:DO-214AA")
      (fields
        (field (name "MANUFACTURER") "Bourns Inc.")
        (field (name "MPN") " 1.5SMBJ30A")
        (field (name "VOLTAGE") "30V")
      )
      (libsource (lib "eagle-import") (part "TVS_?_DO-214AA30V"))
    )
    (comp (ref "D4")
      (value "TVS_DO-214AA_30V")
      (footprint "eagle-import:DO-214AA")
      (fields
        (field (name "MANUFACTURER") "Bourns Inc.")
        (field (name "MPN") " 1.5SMBJ30A")
        (field (name "VOLTAGE") "30V")
      )
      (libsource (lib "eagle-import") (part "TVS_?_DO-214AA30V"))
    )
    (comp (ref "D5")
      (value "TVS_DO-214AA_30V")
      (footprint "eagle-import:DO-214AA")
      (fields
        (field (name "MANUFACTURER") "Bourns Inc.")
        (field (name "MPN") " 1.5SMBJ30A")
        (field (name "VOLTAGE") "30V")
      )
      (libsource (lib "eagle-import") (part "TVS_?_DO-214AA30V"))
    )
    (comp (ref "D101")
      (value "LED_7_SEGMENT_BLUE_DSM7TA")
      (footprint "eagle-import:DSM7T")
      (fields
        (field (name "COLOR") "Blue")
        (field (name "MANUFACTURER") "Visual Communications Company")
        (field (name "MPN") "DSM7TA56106T")
      )
      (libsource (lib "eagle-import") (part "LED_7_SEGMENT_DSM7TABLUE_"))
    )
    (comp (ref "INERTIA")
      (value "TEST_POINT")
      (footprint "eagle-import:5015")
      (fields (field (name "MPN") "5015") (field (name "MANUFACTURER") "Keystone Electronics"))
      (libsource (lib "eagle-import") (part "TEST_POINT"))
    )
    (comp (ref "LS100")
      (value "BUZZER_3_PIN_CPT-3011C-120")
      (footprint "eagle-import:CPT-3011C-120")
      (fields
        (field (name "MANUFACTURER") "CUI Devices")
        (field (name "MPN") "CPT-3011C-120")
        (field (name "VOLTAGE") "12V")
      )
      (libsource (lib "eagle-import") (part "BUZZER_3_PIN_CPT-3011C-120"))
    )
    (comp (ref "R3")
      (value "RESISTOR_0603_41.2K")
      (footprint "eagle-import:0603-RES")
      (fields
        (field (name "MANUFACTURER") "Panasonic Electronic Components")
        (field (name "MPN") " ERJ-PB3B4122V")
        (field (name "POWER") "0.2W")
        (field (name "RESISTANCE") "41.2k")
      )
      (libsource (lib "eagle-import") (part "RESISTOR_?_060341.2K"))
    )
    (comp (ref "R4")
      (value "RESISTOR_0603_41.2K")
      (footprint "eagle-import:0603-RES")
      (fields
        (field (name "MANUFACTURER") "Panasonic Electronic Components")
        (field (name "MPN") " ERJ-PB3B4122V")
        (field (name "POWER") "0.2W")
        (field (name "RESISTANCE") "41.2k")
      )
      (libsource (lib "eagle-import") (part "RESISTOR_?_060341.2K"))
    )
    (comp (ref "R5")
      (value "RESISTOR_0603_41.2K")
      (footprint "eagle-import:0603-RES")
      (fields
        (field (name "MANUFACTURER") "Panasonic Electronic Components")
        (field (name "MPN") " ERJ-PB3B4122V")
        (field (name "POWER") "0.2W")
        (field (name "RESISTANCE") "41.2k")
      )
      (libsource (lib "eagle-import") (part "RESISTOR_?_060341.2K"))
    )
    (comp (ref "R8")
      (value "RESISTOR_0603_5.1K")
      (footprint "eagle-import:0603-RES")
      (fields
        (field (name "MANUFACTURER") "Yageo")
        (field (name "MPN") "RC0603FR-075K1L")
        (field (name "POWER") "0.1W")
        (field (name "RESISTANCE") "5.1k")
      )
      (libsource (lib "eagle-import") (part "RESISTOR_?_06035.1K"))
    )
    (comp (ref "R9")
      (value "RESISTOR_0603_150K")
      (footprint "eagle-import:0603-RES")
      (fields
        (field (name "MANUFACTURER") "Panasonic Electronic Components")
        (field (name "MPN") "ERA-3AEB154V")
        (field (name "POWER") "0.1W")
        (field (name "RESISTANCE") "150k")
      )
      (libsource (lib "eagle-import") (part "RESISTOR_?_0603150K"))
    )
    (comp (ref "R11")
      (value "RESISTOR_0603_10K")
      (footprint "eagle-import:0603-RES")
      (fields
        (field (name "MANUFACTURER") "Panasonic Electronic Components")
        (field (name "MPN") "ERA-3ARB103V")
        (field (name "POWER") "0.1W")
        (field (name "RESISTANCE") "10k")
      )
      (libsource (lib "eagle-import") (part "RESISTOR_?_060310K"))
    )
    (comp (ref "R12")
      (value "RESISTOR_0603_5.1K")
      (footprint "eagle-import:0603-RES")
      (fields
        (field (name "MANUFACTURER") "Yageo")
        (field (name "MPN") "RC0603FR-075K1L")
        (field (name "POWER") "0.1W")
        (field (name "RESISTANCE") "5.1k")
      )
      (libsource (lib "eagle-import") (part "RESISTOR_?_06035.1K"))
    )
    (comp (ref "R13")
      (value "RESISTOR_0603_1.5M")
      (footprint "eagle-import:0603-RES")
      (fields
        (field (name "MANUFACTURER") "Yageo")
        (field (name "MPN") "RC0603FR-071M5L")
        (field (name "POWER") "0.1W")
        (field (name "RESISTANCE") "1.5M")
      )
      (libsource (lib "eagle-import") (part "RESISTOR_?_06031.5M"))
    )
    (comp (ref "R14")
      (value "RESISTOR_0603_5.1K")
      (footprint "eagle-import:0603-RES")
      (fields
        (field (name "MANUFACTURER") "Yageo")
        (field (name "MPN") "RC0603FR-075K1L")
        (field (name "POWER") "0.1W")
        (field (name "RESISTANCE") "5.1k")
      )
      (libsource (lib "eagle-import") (part "RESISTOR_?_06035.1K"))
    )
    (comp (ref "R36")
      (value "RESISTOR_0603_60.4")
      (footprint "eagle-import:0603-RES")
      (fields
        (field (name "MANUFACTURER") "Yageo")
        (field (name "MPN") "RC0603FR-0760R4L")
        (field (name "POWER") "0.1W")
        (field (name "RESISTANCE") "60.4")
      )
      (libsource (lib "eagle-import") (part "RESISTOR_?_060360.4"))
    )
    (comp (ref "R60")
      (value "RESISTOR_0603_60.4")
      (footprint "eagle-import:0603-RES")
      (fields
        (field (name "MANUFACTURER") "Yageo")
        (field (name "MPN") "RC0603FR-0760R4L")
        (field (name "POWER") "0.1W")
        (field (name "RESISTANCE") "60.4")
      )
      (libsource (lib "eagle-import") (part "RESISTOR_?_060360.4"))
    )
    (comp (ref "RN2")
      (value "RESISTOR_NETWORK_4_160")
      (footprint "eagle-import:1206-RES-ARRAY")
      (fields
        (field (name "MANUFACTURER") "Yageo")
        (field (name "MPN") "YC164-JR-07160RL")
        (field (name "POWER") "1/16W")
        (field (name "RESISTANCE") "160")
      )
      (libsource (lib "eagle-import") (part "RESISTOR_NETWORK_4_160"))
    )
    (comp (ref "RN4")
      (value "RESISTOR_NETWORK_4_160")
      (footprint "eagle-import:1206-RES-ARRAY")
      (fields
        (field (name "MANUFACTURER") "Yageo")
        (field (name "MPN") "YC164-JR-07160RL")
        (field (name "POWER") "1/16W")
        (field (name "RESISTANCE") "160")
      )
      (libsource (lib "eagle-import") (part "RESISTOR_NETWORK_4_160"))
    )
    (comp (ref "U3")
      (value "MCP23S08")
      (footprint "eagle-import:SSOP-20")
      (fields (field (name "MPN") "MCP23S08-E/SS") (field (name "MANUFACTURER") "Microchip Technology"))
      (libsource (lib "eagle-import") (part "MCP23S08"))
    )
    (comp (ref "U5")
      (value "RE46C100")
      (footprint "eagle-import:SOIC-08(NARROW,0.15_)")
      (fields (field (name "MPN") " RE46C100S8TF") (field (name "MANUFACTURER") "Microchip Technology"))
      (libsource (lib "eagle-import") (part "RE46C100"))
    )
    (comp (ref "U27")
      (value "TCAN1051HQV-Q1")
      (footprint "eagle-import:SOIC-08(NARROW,0.15_)")
      (fields (field (name "MANUFACTURER") "Texas Instruments") (field (name "MPN") "TCAN1051HGVDRQ1"))
      (libsource (lib "eagle-import") (part "TCAN1051V-Q1HQ"))
    )
    (comp (ref "3V3")
      (value "LED_0603_GREEN_2V2")
      (footprint "eagle-import:0603-LED")
      (fields
        (field (name "COLOR") "Green")
        (field (name "MANUFACTURER") "Kingbright")
        (field (name "MPN") "APT1608SGC")
      )
      (libsource (lib "eagle-import") (part "LED_?_0603GREEN_2V2"))
    )
    (comp (ref "5V")
      (value "LED_0603_BLUE")
      (footprint "eagle-import:0603-LED")
      (fields
        (field (name "COLOR") "Blue")
        (field (name "MANUFACTURER") "Kingbright")
        (field (name "MPN") "APT1608VBC/D")
      )
      (libsource (lib "eagle-import") (part "HyTechDevices - Copy_LED_?_0603BLUE"))
    )
    (comp (ref "12V")
      (value "LED_0603_RED")
      (footprint "eagle-import:0603-LED")
      (fields
        (field (name "COLOR") "Red")
        (field (name "MANUFACTURER") "Kingbright")
        (field (name "MPN") "APT1608SECK/J3-PRV")
      )
      (libsource (lib "eagle-import") (part "HyTechDevices - Copy_LED_?_0603RED"))
    )
    (comp (ref "24V")
      (value "LED_0603_ORANGE")
      (footprint "eagle-import:0603-LED")
      (fields
        (field (name "COLOR") "Orange")
        (field (name "MANUFACTURER") "Kingbright")
        (field (name "MPN") "APT1608SECK")
      )
      (libsource (lib "eagle-import") (part "LED_?_0603ORANGE"))
    )
    (comp (ref "A1")
      (value "VOLTAGE_REGULATOR_MODULE__5V")
      (footprint "eagle-import:OKI-78SR(HORIZONTAL)")
      (fields
        (field (name "MANUFACTURER") "Murata Power Solutions Inc.")
        (field (name "MPN") "OKI-78SR-5/1.5-W36H-C ")
      )
      (libsource (lib "eagle-import") (part "VOLTAGE_REGULATOR_MODULE_?_5V"))
    )
    (comp (ref "A2")
      (value "VOLTAGE_REGULATOR_MODULE__12V")
      (footprint "eagle-import:OKI-78SR(HORIZONTAL)")
      (fields
        (field (name "MANUFACTURER") "Murata Power Solutions Inc.")
        (field (name "MPN") "OKI-78SR-12/1.0-W36H-C")
      )
      (libsource (lib "eagle-import") (part "VOLTAGE_REGULATOR_MODULE_?_12V"))
    )
    (comp (ref "C8")
      (value "CAPACITOR_0805_50V_10UF")
      (footprint "eagle-import:0805-CAP")
      (fields
        (field (name "CAPACITANCE") "10uF")
        (field (name "MANUFACTURER") "Murata")
        (field (name "MPN") " GRM21BR61H106KE43L")
        (field (name "TOLERANCE") "10%")
        (field (name "VOLTAGE") "50V")
      )
      (libsource (lib "eagle-import") (part "CAPACITOR_?_080550V_10UF"))
    )
    (comp (ref "C18")
      (value "CAPACITOR_0603_10V_0.1UF")
      (footprint "eagle-import:0603-CAP")
      (fields
        (field (name "CAPACITANCE") "0.1µF")
        (field (name "MANUFACTURER") "Vishay Vitramon")
        (field (name "MPN") "VJ0603Y104JXQPW1BC")
        (field (name "TOLERANCE") "5%")
        (field (name "VOLTAGE") "10V")
      )
      (libsource (lib "eagle-import") (part "CAPACITOR_?_060310V_0.1UF"))
    )
    (comp (ref "C19")
      (value "CAPACITOR_0603_10V_0.1UF")
      (footprint "eagle-import:0603-CAP")
      (fields
        (field (name "CAPACITANCE") "0.1µF")
        (field (name "MANUFACTURER") "Vishay Vitramon")
        (field (name "MPN") "VJ0603Y104JXQPW1BC")
        (field (name "TOLERANCE") "5%")
        (field (name "VOLTAGE") "10V")
      )
      (libsource (lib "eagle-import") (part "CAPACITOR_?_060310V_0.1UF"))
    )
    (comp (ref "C22")
      (value "CAPACITOR_0603_10V_4.7UF")
      (footprint "eagle-import:0603-CAP")
      (fields
        (field (name "CAPACITANCE") "4.7µF")
        (field (name "MANUFACTURER") "Samsung Electro-Mechanics")
        (field (name "MPN") "CL10A475KP8NNNC")
        (field (name "TOLERANCE") "10%")
        (field (name "VOLTAGE") "10V")
      )
      (libsource (lib "eagle-import") (part "CAPACITOR_?_060310V_4.7UF"))
    )
    (comp (ref "C24")
      (value "CAPACITOR_0805_50V_10UF")
      (footprint "eagle-import:0805-CAP")
      (fields
        (field (name "CAPACITANCE") "10uF")
        (field (name "MANUFACTURER") "Murata")
        (field (name "MPN") " GRM21BR61H106KE43L")
        (field (name "TOLERANCE") "10%")
        (field (name "VOLTAGE") "50V")
      )
      (libsource (lib "eagle-import") (part "CAPACITOR_?_080550V_10UF"))
    )
    (comp (ref "C26")
      (value "CAPACITOR_0603_10V_0.1UF")
      (footprint "eagle-import:0603-CAP")
      (fields
        (field (name "CAPACITANCE") "0.1µF")
        (field (name "MANUFACTURER") "Vishay Vitramon")
        (field (name "MPN") "VJ0603Y104JXQPW1BC")
        (field (name "TOLERANCE") "5%")
        (field (name "VOLTAGE") "10V")
      )
      (libsource (lib "eagle-import") (part "CAPACITOR_?_060310V_0.1UF"))
    )
    (comp (ref "C27")
      (value "CAPACITOR_0603_10V_0.1UF")
      (footprint "eagle-import:0603-CAP")
      (fields
        (field (name "CAPACITANCE") "0.1µF")
        (field (name "MANUFACTURER") "Vishay Vitramon")
        (field (name "MPN") "VJ0603Y104JXQPW1BC")
        (field (name "TOLERANCE") "5%")
        (field (name "VOLTAGE") "10V")
      )
      (libsource (lib "eagle-import") (part "CAPACITOR_?_060310V_0.1UF"))
    )
    (comp (ref "C29")
      (value "CAPACITOR_0603_10V_4.7UF")
      (footprint "eagle-import:0603-CAP")
      (fields
        (field (name "CAPACITANCE") "4.7µF")
        (field (name "MANUFACTURER") "Samsung Electro-Mechanics")
        (field (name "MPN") "CL10A475KP8NNNC")
        (field (name "TOLERANCE") "10%")
        (field (name "VOLTAGE") "10V")
      )
      (libsource (lib "eagle-import") (part "CAPACITOR_?_060310V_4.7UF"))
    )
    (comp (ref "C33")
      (value "CAPACITOR_0603_25V_10UF")
      (footprint "eagle-import:0603-CAP")
      (fields
        (field (name "CAPACITANCE") "10µF")
        (field (name "MANUFACTURER") "Murata Electronics")
        (field (name "MPN") "GRM188R61E106MA73D")
        (field (name "TOLERANCE") "20%")
        (field (name "VOLTAGE") "25V")
      )
      (libsource (lib "eagle-import") (part "CAPACITOR_?_060325V_10UF"))
    )
    (comp (ref "C40")
      (value "CAPACITOR_0805_50V_10UF")
      (footprint "eagle-import:0805-CAP")
      (fields
        (field (name "CAPACITANCE") "10uF")
        (field (name "MANUFACTURER") "Murata")
        (field (name "MPN") " GRM21BR61H106KE43L")
        (field (name "TOLERANCE") "10%")
        (field (name "VOLTAGE") "50V")
      )
      (libsource (lib "eagle-import") (part "CAPACITOR_?_080550V_10UF"))
    )
    (comp (ref "D1")
      (value "USBLC6-2SC6")
      (footprint "eagle-import:SOT-23-6")
      (fields (field (name "MPN") "USBLC6-2SC6") (field (name "MANUFACTURER") "STMicroelectronics"))
      (libsource (lib "eagle-import") (part "USBLC6-2SC6"))
    )
    (comp (ref "D2")
      (value "SCHOTTKY__15V")
      (footprint "eagle-import:DO-214BA")
      (fields
        (field (name "MANUFACTURER") "Microchip Technology")
        (field (name "MPN") "LSM115JE3/TR13")
        (field (name "VOLTAGE") "15V")
      )
      (libsource (lib "eagle-import") (part "SCHOTTKY_?_15V"))
    )
    (comp (ref "D6")
      (value "TVS_DO-214AA_30V")
      (footprint "eagle-import:DO-214AA")
      (fields
        (field (name "MANUFACTURER") "Bourns Inc.")
        (field (name "MPN") " 1.5SMBJ30A")
        (field (name "VOLTAGE") "30V")
      )
      (libsource (lib "eagle-import") (part "TVS_?_DO-214AA30V"))
    )
    (comp (ref "J1")
      (value "CONNECTOR-4_μF_S_RA_")
      (footprint "eagle-import:MOLEX_MICROFIT_SMD_RIGHTANGLE_04_DUAL")
      (fields (field (name "MPN") "0430450411") (field (name "MANUFACTURER") "Molex"))
      (libsource (lib "eagle-import") (part "CONNECTOR-4_?_μF_S_RA"))
    )
    (comp (ref "J2")
      (value "CONNECTOR-8_μF_S_RA_")
      (footprint "eagle-import:MOLEX_MICROFIT_SMD_RIGHTANGLE_08_DUAL")
      (fields (field (name "MPN") "0430450811") (field (name "MANUFACTURER") "Molex"))
      (libsource (lib "eagle-import") (part "CONNECTOR-8_?_μF_S_RA"))
    )
    (comp (ref "J3")
      (value "CONNECTOR-4_μF_S_RA_")
      (footprint "eagle-import:MOLEX_MICROFIT_SMD_RIGHTANGLE_04_DUAL")
      (fields (field (name "MPN") "0430450411") (field (name "MANUFACTURER") "Molex"))
      (libsource (lib "eagle-import") (part "CONNECTOR-4_?_μF_S_RA"))
    )
    (comp (ref "J4")
      (value "CONNECTOR-6_μF_S_RA_")
      (footprint "eagle-import:MOLEX_MICROFIT_SMD_RIGHTANGLE_06_DUAL")
      (fields (field (name "MPN") "0430450611") (field (name "MANUFACTURER") "Molex"))
      (libsource (lib "eagle-import") (part "CONNECTOR-6_?_μF_S_RA"))
    )
    (comp (ref "J5")
      (value "CONNECTOR-10__")
      (footprint "eagle-import:5051101092")
      (fields (field (name "MPN") "  5051101092") (field (name "MANUFACTURER") "MOLEX"))
      (libsource (lib "eagle-import") (part "CONNECTOR-10_?_"))
    )
    (comp (ref "J7")
      (value "CONNECTOR-4_FD19_0492_")
      (footprint "eagle-import:5051100492")
      (fields (field (name "MPN") "505110-0492") (field (name "MANUFACTURER") "Molex"))
      (libsource (lib "eagle-import") (part "CONNECTOR-4_?_FD19_0492"))
    )
    (comp (ref "J8")
      (value "USB4110")
      (footprint "eagle-import:USB4110")
      (fields (field (name "MPN") "USB4110 ") (field (name "MANUFACTURER") "GCT"))
      (libsource (lib "eagle-import") (part "USB4110"))
    )
    (comp (ref "J9")
      (value "CONNECTOR-4_FD19_0492_")
      (footprint "eagle-import:5051100492")
      (fields (field (name "MPN") "505110-0492") (field (name "MANUFACTURER") "Molex"))
      (libsource (lib "eagle-import") (part "CONNECTOR-4_?_FD19_0492"))
    )
    (comp (ref "J10")
      (value "CONNECTOR-10__")
      (footprint "eagle-import:5051101092")
      (fields (field (name "MPN") "  5051101092") (field (name "MANUFACTURER") "MOLEX"))
      (libsource (lib "eagle-import") (part "CONNECTOR-10_?_"))
    )
    (comp (ref "J11")
      (value "CONNECTOR-8_μF_S_RA_")
      (footprint "eagle-import:MOLEX_MICROFIT_SMD_RIGHTANGLE_08_DUAL")
      (fields (field (name "MPN") "0430450811") (field (name "MANUFACTURER") "Molex"))
      (libsource (lib "eagle-import") (part "CONNECTOR-8_?_μF_S_RA"))
    )
    (comp (ref "MCU_LED")
      (value "LED_0603_GREEN_2V2")
      (footprint "eagle-import:0603-LED")
      (fields
        (field (name "COLOR") "Green")
        (field (name "MANUFACTURER") "Kingbright")
        (field (name "MPN") "APT1608SGC")
      )
      (libsource (lib "eagle-import") (part "LED_?_0603GREEN_2V2"))
    )
    (comp (ref "R1")
      (value "RESISTOR_0603_240")
      (footprint "eagle-import:0603-RES")
      (fields
        (field (name "MANUFACTURER") "Yageo")
        (field (name "MPN") "RC0603FR-07240RL")
        (field (name "POWER") "0.1W")
        (field (name "RESISTANCE") "240")
      )
      (libsource (lib "eagle-import") (part "RESISTOR_?_0603240"))
    )
    (comp (ref "R2")
      (value "RESISTOR_0603_1K")
      (footprint "eagle-import:0603-RES")
      (fields
        (field (name "MANUFACTURER") "TE Connectivity Passive Product")
        (field (name "MPN") " CPF-A-0603B1K0E")
        (field (name "POWER") "0.0625W")
        (field (name "RESISTANCE") "1k")
      )
      (libsource (lib "eagle-import") (part "RESISTOR_?_06031K"))
    )
    (comp (ref "R6")
      (value "RESISTOR_0603_240")
      (footprint "eagle-import:0603-RES")
      (fields
        (field (name "MANUFACTURER") "Yageo")
        (field (name "MPN") "RC0603FR-07240RL")
        (field (name "POWER") "0.1W")
        (field (name "RESISTANCE") "240")
      )
      (libsource (lib "eagle-import") (part "RESISTOR_?_0603240"))
    )
    (comp (ref "R17")
      (value "RESISTOR_0603_5.1K")
      (footprint "eagle-import:0603-RES")
      (fields
        (field (name "MANUFACTURER") "Yageo")
        (field (name "MPN") "RC0603FR-075K1L")
        (field (name "POWER") "0.1W")
        (field (name "RESISTANCE") "5.1k")
      )
      (libsource (lib "eagle-import") (part "RESISTOR_?_06035.1K"))
    )
    (comp (ref "R18")
      (value "RESISTOR_0603_5.1K")
      (footprint "eagle-import:0603-RES")
      (fields
        (field (name "MANUFACTURER") "Yageo")
        (field (name "MPN") "RC0603FR-075K1L")
        (field (name "POWER") "0.1W")
        (field (name "RESISTANCE") "5.1k")
      )
      (libsource (lib "eagle-import") (part "RESISTOR_?_06035.1K"))
    )
    (comp (ref "R19")
      (value "RESISTOR_0603_30")
      (footprint "eagle-import:0603-RES")
      (fields
        (field (name "MANUFACTURER") "Panasonic Electronic Components")
        (field (name "MPN") "ERJ-UP3F30R0V")
        (field (name "POWER") "0.25W")
        (field (name "RESISTANCE") "30")
      )
      (libsource (lib "eagle-import") (part "RESISTOR_?_060330"))
    )
    (comp (ref "R20")
      (value "RESISTOR_0603_30")
      (footprint "eagle-import:0603-RES")
      (fields
        (field (name "MANUFACTURER") "Panasonic Electronic Components")
        (field (name "MPN") "ERJ-UP3F30R0V")
        (field (name "POWER") "0.25W")
        (field (name "RESISTANCE") "30")
      )
      (libsource (lib "eagle-import") (part "RESISTOR_?_060330"))
    )
    (comp (ref "R21")
      (value "RESISTOR_0603_180")
      (footprint "eagle-import:0603-RES")
      (fields
        (field (name "MANUFACTURER") "Yageo")
        (field (name "MPN") "RC0603FR-07180RL")
        (field (name "POWER") "0.1W")
        (field (name "RESISTANCE") "180")
      )
      (libsource (lib "eagle-import") (part "RESISTOR_?_0603180"))
    )
    (comp (ref "R83")
      (value "RESISTOR_0603_3.3K")
      (footprint "eagle-import:0603-RES")
      (fields
        (field (name "MANUFACTURER") "Panasonic Electronic Components")
        (field (name "MPN") "ERJ-PB3D3301V")
        (field (name "POWER") "0.3W")
        (field (name "RESISTANCE") "3.3k")
      )
      (libsource (lib "eagle-import") (part "RESISTOR_?_06033.3K"))
    )
    (comp (ref "SPI1_MOSI")
      (value "TEST_POINT")
      (footprint "eagle-import:5015")
      (fields (field (name "MPN") "5015") (field (name "MANUFACTURER") "Keystone Electronics"))
      (libsource (lib "eagle-import") (part "TEST_POINT"))
    )
    (comp (ref "SPI1_SCK")
      (value "TEST_POINT")
      (footprint "eagle-import:5015")
      (fields (field (name "MPN") "5015") (field (name "MANUFACTURER") "Keystone Electronics"))
      (libsource (lib "eagle-import") (part "TEST_POINT"))
    )
    (comp (ref "SPI3_MOSI")
      (value "TEST_POINT")
      (footprint "eagle-import:5015")
      (fields (field (name "MPN") "5015") (field (name "MANUFACTURER") "Keystone Electronics"))
      (libsource (lib "eagle-import") (part "TEST_POINT"))
    )
    (comp (ref "SPI3_SCK")
      (value "TEST_POINT")
      (footprint "eagle-import:5015")
      (fields (field (name "MPN") "5015") (field (name "MANUFACTURER") "Keystone Electronics"))
      (libsource (lib "eagle-import") (part "TEST_POINT"))
    )
    (comp (ref "TP_3.3V")
      (value "TEST_POINT")
      (footprint "eagle-import:5015")
      (fields
        (field (name "MPN") "5015")
        (field (name "MANUFACTURER") "Keystone Electronics")
        (field (name "SIGNAL") "+3V3")
      )
      (libsource (lib "eagle-import") (part "TEST_POINT"))
    )
    (comp (ref "TP_5V")
      (value "TEST_POINT")
      (footprint "eagle-import:5015")
      (fields (field (name "MPN") "5015") (field (name "MANUFACTURER") "Keystone Electronics"))
      (libsource (lib "eagle-import") (part "TEST_POINT"))
    )
    (comp (ref "TP_12V")
      (value "TEST_POINT")
      (footprint "eagle-import:5015")
      (fields (field (name "MPN") "5015") (field (name "MANUFACTURER") "Keystone Electronics"))
      (libsource (lib "eagle-import") (part "TEST_POINT"))
    )
    (comp (ref "TP_24V")
      (value "TEST_POINT")
      (footprint "eagle-import:5015")
      (fields (field (name "MPN") "5015") (field (name "MANUFACTURER") "Keystone Electronics"))
      (libsource (lib "eagle-import") (part "TEST_POINT"))
    )
    (comp (ref "TP_GND")
      (value "TEST_POINT")
      (footprint "eagle-import:5015")
      (fields (field (name "MPN") "5015") (field (name "MANUFACTURER") "Keystone Electronics"))
      (libsource (lib "eagle-import") (part "TEST_POINT"))
    )
    (comp (ref "U$12")
      (value "JUMPER_3PIN")
      (footprint "eagle-import:1X03")
      (libsource (lib "eagle-import") (part "JUMPER_3PIN"))
    )
    (comp (ref "U17")
      (value "VOLTAGE_REGULATOR_SOT-223_3.3V")
      (footprint "eagle-import:SOT-223")
      (fields (field (name "MANUFACTURER") "Texas Instruments") (field (name "MPN") "LMS8117AMP-3.3/NOPB"))
      (libsource (lib "eagle-import") (part "VOLTAGE_REGULATOR_?_SOT-2233.3V"))
    )
    (comp (ref "XF1")
      (value "FUSE_HOLDER_MINIBLADESMD")
      (footprint "eagle-import:3588")
      (fields (field (name "MANUFACTURER") "Keystone Electronics") (field (name "MPN") "3588"))
      (libsource (lib "eagle-import") (part "FUSE_HOLDER_SMDMINIBLADE"))
    )
  )
  (nets
    (net (code "1") (name "+3V3") (class "Default")
      (node (ref "3V3") (pin "2") (pinfunction "A_2") (pintype "passive"))
      (node (ref "C13") (pin "1") (pinfunction "1_1") (pintype "passive"))
      (node (ref "C20") (pin "2") (pinfunction "2_2") (pintype "passive"))
      (node (ref "C28") (pin "1") (pinfunction "1_1") (pintype "passive"))
      (node (ref "C29") (pin "1") (pinfunction "1_1") (pintype "passive"))
      (node (ref "C34") (pin "2") (pinfunction "2_2") (pintype "passive"))
      (node (ref "C4") (pin "1") (pinfunction "1_1") (pintype "passive"))
      (node (ref "C5") (pin "1") (pinfunction "1_1") (pintype "passive"))
      (node (ref "C6") (pin "1") (pinfunction "1_1") (pintype "passive"))
      (node (ref "C7") (pin "1") (pinfunction "1_1") (pintype "passive"))
      (node (ref "C9") (pin "1") (pinfunction "1_1") (pintype "passive"))
      (node (ref "R7") (pin "2") (pinfunction "2_2") (pintype "passive"))
      (node (ref "S2") (pin "1") (pinfunction "1_1") (pintype "bidirectional"))
      (node (ref "TP_3.3V") (pin "1") (pinfunction "1_1") (pintype "passive"))
      (node (ref "U$6") (pin "1") (pinfunction "VCCA_1") (pintype "power_in"))
      (node (ref "U$6") (pin "5") (pinfunction "DIR_5") (pintype "input"))
      (node (ref "U16") (pin "P$1") (pinfunction "VBAT_P$1") (pintype "power_in"))
      (node (ref "U16") (pin "P$13") (pinfunction "VDDA/VREF+_P$13") (pintype "power_in"))
      (node (ref "U16") (pin "P$19") (pinfunction "VDD_P$19") (pintype "power_in"))
      (node (ref "U16") (pin "P$32") (pinfunction "VDD1_P$32") (pintype "power_in"))
      (node (ref "U16") (pin "P$48") (pinfunction "VDD2_P$48") (pintype "power_in"))
      (node (ref "U16") (pin "P$64") (pinfunction "VDD3_P$64") (pintype "power_in"))
      (node (ref "U17") (pin "2") (pinfunction "OUT_2") (pintype "power_in"))
      (node (ref "U17") (pin "4") (pinfunction "OUT_4") (pintype "power_in"))
      (node (ref "U27") (pin "5") (pinfunction "VIO_5") (pintype "power_in"))
    )
    (net (code "2") (name "+5V") (class "Default")
      (node (ref "5V") (pin "2") (pinfunction "A_2") (pintype "passive"))
      (node (ref "C10") (pin "1") (pinfunction "1_1") (pintype "passive"))
      (node (ref "C11") (pin "1") (pinfunction "1_1") (pintype "passive"))
      (node (ref "C12") (pin "1") (pinfunction "1_1") (pintype "passive"))
      (node (ref "C16") (pin "1") (pinfunction "1_1") (pintype "passive"))
      (node (ref "C21") (pin "1") (pinfunction "1_1") (pintype "passive"))
      (node (ref "C22") (pin "1") (pinfunction "1_1") (pintype "passive"))
      (node (ref "C38") (pin "2") (pinfunction "2_2") (pintype "passive"))
      (node (ref "C39") (pin "2") (pinfunction "2_2") (pintype "passive"))
      (node (ref "D1") (pin "5") (pinfunction "V-BUS_5") (pintype "power_in"))
      (node (ref "D101") (pin "3") (pinfunction "VDD_3") (pintype "power_in"))
      (node (ref "D101") (pin "8") (pinfunction "VDD_8") (pintype "power_in"))
      (node (ref "D2") (pin "2") (pinfunction "C_2") (pintype "passive"))
      (node (ref "J8") (pin "P$11") (pinfunction "VBUS_P$11") (pintype "power_in"))
      (node (ref "J8") (pin "P$2") (pinfunction "VBUS_P$2") (pintype "power_in"))
      (node (ref "TP_5V") (pin "1") (pinfunction "1_1") (pintype "passive"))
      (node (ref "U$12") (pin "3") (pinfunction "3_3") (pintype "passive"))
      (node (ref "U$6") (pin "8") (pinfunction "VCCB_8") (pintype "power_in"))
      (node (ref "U1") (pin "1") (pinfunction "VDD_1") (pintype "power_in"))
      (node (ref "U10") (pin "1") (pinfunction "VDD_1") (pintype "power_in"))
      (node (ref "U12") (pin "1") (pinfunction "VDD_1") (pintype "power_in"))
      (node (ref "U13") (pin "1") (pinfunction "VDD_1") (pintype "power_in"))
      (node (ref "U14") (pin "1") (pinfunction "VDD_1") (pintype "power_in"))
      (node (ref "U15") (pin "1") (pinfunction "VDD_1") (pintype "power_in"))
      (node (ref "U17") (pin "3") (pinfunction "IN_3") (pintype "power_in"))
      (node (ref "U2") (pin "1") (pinfunction "VDD_1") (pintype "power_in"))
      (node (ref "U27") (pin "3") (pinfunction "VDD_3") (pintype "power_in"))
      (node (ref "U3") (pin "20") (pinfunction "VDD_20") (pintype "power_in"))
      (node (ref "U3") (pin "6") (pinfunction "~{RESET}_6") (pintype "input"))
      (node (ref "U4") (pin "1") (pinfunction "VDD_1") (pintype "power_in"))
      (node (ref "U6") (pin "1") (pinfunction "VDD_1") (pintype "power_in"))
      (node (ref "U7") (pin "1") (pinfunction "VDD_1") (pintype "power_in"))
      (node (ref "U8") (pin "1") (pinfunction "VDD_1") (pintype "power_in"))
      (node (ref "U9") (pin "1") (pinfunction "VDD_1") (pintype "power_in"))
    )
    (net (code "3") (name "+12V") (class "Default")
      (node (ref "12V") (pin "2") (pinfunction "A_2") (pintype "passive"))
      (node (ref "A2") (pin "3") (pinfunction "OUT_3") (pintype "power_in"))
      (node (ref "C15") (pin "2") (pinfunction "2_2") (pintype "passive"))
      (node (ref "C40") (pin "1") (pinfunction "1_1") (pintype "passive"))
      (node (ref "J1") (pin "1") (pinfunction "1_1") (pintype "passive"))
      (node (ref "TP_12V") (pin "1") (pinfunction "1_1") (pintype "passive"))
      (node (ref "U5") (pin "2") (pinfunction "VDD_2") (pintype "power_in"))
    )
    (net (code "4") (name "+24V") (class "Default")
      (node (ref "24V") (pin "2") (pinfunction "A_2") (pintype "passive"))
      (node (ref "A1") (pin "1") (pinfunction "IN_1") (pintype "power_in"))
      (node (ref "A2") (pin "1") (pinfunction "IN_1") (pintype "power_in"))
      (node (ref "C24") (pin "1") (pinfunction "1_1") (pintype "passive"))
      (node (ref "C8") (pin "1") (pinfunction "1_1") (pintype "passive"))
      (node (ref "TP_24V") (pin "1") (pinfunction "1_1") (pintype "passive"))
      (node (ref "XF1") (pin "3") (pinfunction "2_3") (pintype "passive"))
      (node (ref "XF1") (pin "4") (pinfunction "2_4") (pintype "passive"))
    )
    (net (code "5") (name "5V_IN") (class "Default")
      (node (ref "A1") (pin "3") (pinfunction "OUT_3") (pintype "power_in"))
      (node (ref "C33") (pin "1") (pinfunction "1_1") (pintype "passive"))
      (node (ref "D2") (pin "1") (pinfunction "A_1") (pintype "passive"))
      (node (ref "U$12") (pin "1") (pinfunction "1_1") (pintype "passive"))
    )
    (net (code "6") (name "7SEG_LOAD") (class "Default")
      (node (ref "U16") (pin "P$50") (pinfunction "PA15_P$50") (pintype "bidirectional"))
      (node (ref "U3") (pin "7") (pinfunction "~{CS}_7") (pintype "input"))
    )
    (net (code "7") (name "24VIN") (class "Default")
      (node (ref "D6") (pin "2") (pinfunction "C_2") (pintype "passive"))
      (node (ref "J2") (pin "1") (pinfunction "1_1") (pintype "passive"))
      (node (ref "XF1") (pin "1") (pinfunction "1_1") (pintype "passive"))
      (node (ref "XF1") (pin "2") (pinfunction "1_2") (pintype "passive"))
    )
    (net (code "8") (name "BOTS") (class "Default")
      (node (ref "BOTS") (pin "1") (pinfunction "1_1") (pintype "passive"))
      (node (ref "D4") (pin "2") (pinfunction "C_2") (pintype "passive"))
      (node (ref "J2") (pin "5") (pinfunction "5_5") (pintype "passive"))
      (node (ref "R4") (pin "1") (pinfunction "1_1") (pintype "passive"))
    )
    (net (code "9") (name "BOTS_READ") (class "Default")
      (node (ref "R12") (pin "1") (pinfunction "1_1") (pintype "passive"))
      (node (ref "R4") (pin "2") (pinfunction "2_2") (pintype "passive"))
      (node (ref "U16") (pin "P$58") (pinfunction "PB6_P$58") (pintype "bidirectional"))
    )
    (net (code "10") (name "BRB") (class "Default")
      (node (ref "BRB") (pin "1") (pinfunction "1_1") (pintype "passive"))
      (node (ref "D5") (pin "2") (pinfunction "C_2") (pintype "passive"))
      (node (ref "J2") (pin "2") (pinfunction "2_2") (pintype "passive"))
      (node (ref "R5") (pin "1") (pinfunction "1_1") (pintype "passive"))
    )
    (net (code "11") (name "BRB_READ") (class "Default")
      (node (ref "R14") (pin "1") (pinfunction "1_1") (pintype "passive"))
      (node (ref "R5") (pin "2") (pinfunction "2_2") (pintype "passive"))
      (node (ref "U16") (pin "P$57") (pinfunction "PB5_P$57") (pintype "bidirectional"))
    )
    (net (code "12") (name "BTN_DIM_READ") (class "Default")
      (node (ref "J4") (pin "5") (pinfunction "5_5") (pintype "passive"))
      (node (ref "U16") (pin "P$40") (pinfunction "PC9_P$40") (pintype "bidirectional"))
    )
    (net (code "13") (name "BTN_MC_CYCLE_READ") (class "Default")
      (node (ref "J4") (pin "3") (pinfunction "3_3") (pintype "passive"))
      (node (ref "U16") (pin "P$39") (pinfunction "PC8_P$39") (pintype "bidirectional"))
    )
    (net (code "14") (name "BTN_MODE_READ") (class "Default")
      (node (ref "J4") (pin "2") (pinfunction "2_2") (pintype "passive"))
      (node (ref "U16") (pin "P$54") (pinfunction "PD2_P$54") (pintype "bidirectional"))
    )
    (net (code "15") (name "BTN_PRESET_READ") (class "Default")
      (node (ref "J4") (pin "4") (pinfunction "4_4") (pintype "passive"))
      (node (ref "U16") (pin "P$41") (pinfunction "PA8_P$41") (pintype "bidirectional"))
    )
    (net (code "16") (name "BTN_START_READ") (class "Default")
      (node (ref "J4") (pin "1") (pinfunction "1_1") (pintype "passive"))
      (node (ref "U16") (pin "P$53") (pinfunction "PC12_P$53") (pintype "bidirectional"))
    )
    (net (code "17") (name "BUZZER_CTRL") (class "Default")
      (node (ref "R11") (pin "2") (pinfunction "2_2") (pintype "passive"))
      (node (ref "U16") (pin "P$2") (pinfunction "PC13_P$2") (pintype "bidirectional"))
      (node (ref "U5") (pin "8") (pinfunction "EN_8") (pintype "input"))
    )
    (net (code "18") (name "CANH") (class "Default")
      (node (ref "J1") (pin "2") (pinfunction "2_2") (pintype "passive"))
      (node (ref "J2") (pin "4") (pinfunction "4_4") (pintype "passive"))
      (node (ref "R36") (pin "2") (pinfunction "2_2") (pintype "passive"))
      (node (ref "U27") (pin "7") (pinfunction "CANH_7") (pintype "output"))
    )
    (net (code "19") (name "CANL") (class "Default")
      (node (ref "J1") (pin "3") (pinfunction "3_3") (pintype "passive"))
      (node (ref "J2") (pin "3") (pinfunction "3_3") (pintype "passive"))
      (node (ref "R60") (pin "2") (pinfunction "2_2") (pintype "passive"))
      (node (ref "U27") (pin "6") (pinfunction "CANL_6") (pintype "bidirectional"))
    )
    (net (code "20") (name "DIAL_AUTOCROSS") (class "Default")
      (node (ref "J11") (pin "5") (pinfunction "5_5") (pintype "passive"))
      (node (ref "U16") (pin "P$38") (pinfunction "PC7_P$38") (pintype "bidirectional"))
    )
    (net (code "21") (name "DIAL_ENDURANCE") (class "Default")
      (node (ref "J11") (pin "4") (pinfunction "4_4") (pintype "passive"))
      (node (ref "U16") (pin "P$33") (pinfunction "PB12_P$33") (pintype "bidirectional"))
    )
    (net (code "22") (name "DIAL_LAUNCH") (class "Default")
      (node (ref "J11") (pin "7") (pinfunction "7_7") (pintype "passive"))
      (node (ref "U16") (pin "P$36") (pinfunction "PB15_P$36") (pintype "bidirectional"))
    )
    (net (code "23") (name "DIAL_MODE_1") (class "Default")
      (node (ref "J11") (pin "3") (pinfunction "3_3") (pintype "passive"))
      (node (ref "U16") (pin "P$34") (pinfunction "PB13_P$34") (pintype "bidirectional"))
    )
    (net (code "24") (name "DIAL_MODE_2") (class "Default")
      (node (ref "J11") (pin "2") (pinfunction "2_2") (pintype "passive"))
      (node (ref "U16") (pin "P$35") (pinfunction "PB14_P$35") (pintype "bidirectional"))
    )
    (net (code "25") (name "DIAL_SKIDPAD") (class "Default")
      (node (ref "J11") (pin "6") (pinfunction "6_6") (pintype "passive"))
      (node (ref "U16") (pin "P$37") (pinfunction "PC6_P$37") (pintype "bidirectional"))
    )
    (net (code "26") (name "DISP_5V") (class "Default")
      (node (ref "C18") (pin "1") (pinfunction "1_1") (pintype "passive"))
      (node (ref "C19") (pin "1") (pinfunction "1_1") (pintype "passive"))
      (node (ref "C26") (pin "1") (pinfunction "1_1") (pintype "passive"))
      (node (ref "C27") (pin "1") (pinfunction "1_1") (pintype "passive"))
      (node (ref "J10") (pin "7") (pinfunction "5_7") (pintype "passive"))
      (node (ref "J10") (pin "8") (pinfunction "6_8") (pintype "passive"))
      (node (ref "J10") (pin "9") (pinfunction "7_9") (pintype "passive"))
      (node (ref "J5") (pin "7") (pinfunction "5_7") (pintype "passive"))
      (node (ref "J5") (pin "8") (pinfunction "6_8") (pintype "passive"))
      (node (ref "J5") (pin "9") (pinfunction "7_9") (pintype "passive"))
      (node (ref "J7") (pin "1") (pinfunction "1_1") (pintype "passive"))
      (node (ref "J7") (pin "2") (pinfunction "2_2") (pintype "passive"))
      (node (ref "J9") (pin "1") (pinfunction "1_1") (pintype "passive"))
      (node (ref "J9") (pin "2") (pinfunction "2_2") (pintype "passive"))
      (node (ref "U$12") (pin "2") (pinfunction "2_2") (pintype "passive"))
    )
    (net (code "27") (name "GND") (class "Default")
      (node (ref "A1") (pin "2") (pinfunction "GND_2") (pintype "power_in"))
      (node (ref "A2") (pin "2") (pinfunction "GND_2") (pintype "power_in"))
      (node (ref "C1") (pin "2") (pinfunction "2_2") (pintype "passive"))
      (node (ref "C10") (pin "2") (pinfunction "2_2") (pintype "passive"))
      (node (ref "C11") (pin "2") (pinfunction "2_2") (pintype "passive"))
      (node (ref "C12") (pin "2") (pinfunction "2_2") (pintype "passive"))
      (node (ref "C13") (pin "2") (pinfunction "2_2") (pintype "passive"))
      (node (ref "C14") (pin "2") (pinfunction "2_2") (pintype "passive"))
      (node (ref "C15") (pin "1") (pinfunction "1_1") (pintype "passive"))
      (node (ref "C16") (pin "2") (pinfunction "2_2") (pintype "passive"))
      (node (ref "C18") (pin "2") (pinfunction "2_2") (pintype "passive"))
      (node (ref "C19") (pin "2") (pinfunction "2_2") (pintype "passive"))
      (node (ref "C2") (pin "2") (pinfunction "2_2") (pintype "passive"))
      (node (ref "C20") (pin "1") (pinfunction "1_1") (pintype "passive"))
      (node (ref "C21") (pin "2") (pinfunction "2_2") (pintype "passive"))
      (node (ref "C22") (pin "2") (pinfunction "2_2") (pintype "passive"))
      (node (ref "C24") (pin "2") (pinfunction "2_2") (pintype "passive"))
      (node (ref "C25") (pin "1") (pinfunction "1_1") (pintype "passive"))
      (node (ref "C26") (pin "2") (pinfunction "2_2") (pintype "passive"))
      (node (ref "C27") (pin "2") (pinfunction "2_2") (pintype "passive"))
      (node (ref "C28") (pin "2") (pinfunction "2_2") (pintype "passive"))
      (node (ref "C29") (pin "2") (pinfunction "2_2") (pintype "passive"))
      (node (ref "C3") (pin "2") (pinfunction "2_2") (pintype "passive"))
      (node (ref "C33") (pin "2") (pinfunction "2_2") (pintype "passive"))
      (node (ref "C34") (pin "1") (pinfunction "1_1") (pintype "passive"))
      (node (ref "C38") (pin "1") (pinfunction "1_1") (pintype "passive"))
      (node (ref "C39") (pin "1") (pinfunction "1_1") (pintype "passive"))
      (node (ref "C4") (pin "2") (pinfunction "2_2") (pintype "passive"))
      (node (ref "C40") (pin "2") (pinfunction "2_2") (pintype "passive"))
      (node (ref "C5") (pin "2") (pinfunction "2_2") (pintype "passive"))
      (node (ref "C6") (pin "2") (pinfunction "2_2") (pintype "passive"))
      (node (ref "C7") (pin "2") (pinfunction "2_2") (pintype "passive"))
      (node (ref "C8") (pin "2") (pinfunction "2_2") (pintype "passive"))
      (node (ref "C9") (pin "2") (pinfunction "2_2") (pintype "passive"))
      (node (ref "D1") (pin "2") (pinfunction "GND_2") (pintype "power_in"))
      (node (ref "D3") (pin "1") (pinfunction "A_1") (pintype "passive"))
      (node (ref "D4") (pin "1") (pinfunction "A_1") (pintype "passive"))
      (node (ref "D5") (pin "1") (pinfunction "A_1") (pintype "passive"))
      (node (ref "D6") (pin "1") (pinfunction "A_1") (pintype "passive"))
      (node (ref "J1") (pin "4") (pinfunction "4_4") (pintype "passive"))
      (node (ref "J10") (pin "11") (pinfunction "9_11") (pintype "passive"))
      (node (ref "J10") (pin "12") (pinfunction "10_12") (pintype "passive"))
      (node (ref "J11") (pin "8") (pinfunction "8_8") (pintype "passive"))
      (node (ref "J2") (pin "8") (pinfunction "8_8") (pintype "passive"))
      (node (ref "J3") (pin "4") (pinfunction "4_4") (pintype "passive"))
      (node (ref "J4") (pin "6") (pinfunction "6_6") (pintype "passive"))
      (node (ref "J5") (pin "11") (pinfunction "9_11") (pintype "passive"))
      (node (ref "J5") (pin "12") (pinfunction "10_12") (pintype "passive"))
      (node (ref "J8") (pin "P$1") (pinfunction "GND_P$1") (pintype "power_in"))
      (node (ref "J8") (pin "P$12") (pinfunction "GND_P$12") (pintype "power_in"))
      (node (ref "J8") (pin "S$1") (pinfunction "SHELL_S$1") (pintype "power_in"))
      (node (ref "J8") (pin "S$2") (pinfunction "SHELL_S$2") (pintype "power_in"))
      (node (ref "J8") (pin "S$3") (pinfunction "SHELL_S$3") (pintype "power_in"))
      (node (ref "J8") (pin "S$4") (pinfunction "SHELL_S$4") (pintype "power_in"))
      (node (ref "R1") (pin "1") (pinfunction "1_1") (pintype "passive"))
      (node (ref "R11") (pin "1") (pinfunction "1_1") (pintype "passive"))
      (node (ref "R12") (pin "2") (pinfunction "2_2") (pintype "passive"))
      (node (ref "R14") (pin "2") (pinfunction "2_2") (pintype "passive"))
      (node (ref "R16") (pin "1") (pinfunction "1_1") (pintype "passive"))
      (node (ref "R17") (pin "1") (pinfunction "1_1") (pintype "passive"))
      (node (ref "R18") (pin "1") (pinfunction "1_1") (pintype "passive"))
      (node (ref "R19") (pin "1") (pinfunction "1_1") (pintype "passive"))
      (node (ref "R2") (pin "1") (pinfunction "1_1") (pintype "passive"))
      (node (ref "R20") (pin "1") (pinfunction "1_1") (pintype "passive"))
      (node (ref "R21") (pin "1") (pinfunction "1_1") (pintype "passive"))
      (node (ref "R6") (pin "1") (pinfunction "1_1") (pintype "passive"))
      (node (ref "R8") (pin "2") (pinfunction "2_2") (pintype "passive"))
      (node (ref "R83") (pin "1") (pinfunction "1_1") (pintype "passive"))
      (node (ref "S1") (pin "3") (pinfunction "S_3") (pintype "passive"))
      (node (ref "S1") (pin "4") (pinfunction "S_4") (pintype "passive"))
      (node (ref "S2") (pin "2") (pinfunction "2_2") (pintype "bidirectional"))
      (node (ref "TP_GND") (pin "1") (pinfunction "1_1") (pintype "passive"))
      (node (ref "U$6") (pin "4") (pinfunction "GND_4") (pintype "bidirectional"))
      (node (ref "U1") (pin "3") (pinfunction "GND_3") (pintype "power_in"))
      (node (ref "U10") (pin "3") (pinfunction "GND_3") (pintype "power_in"))
      (node (ref "U12") (pin "3") (pinfunction "GND_3") (pintype "power_in"))
      (node (ref "U13") (pin "3") (pinfunction "GND_3") (pintype "power_in"))
      (node (ref "U14") (pin "3") (pinfunction "GND_3") (pintype "power_in"))
      (node (ref "U15") (pin "3") (pinfunction "GND_3") (pintype "power_in"))
      (node (ref "U16") (pin "P$12") (pinfunction "VSSA/VREF-_P$12") (pintype "power_in"))
      (node (ref "U16") (pin "P$18") (pinfunction "VSS_P$18") (pintype "power_in"))
      (node (ref "U16") (pin "P$31") (pinfunction "VSS1_P$31") (pintype "power_in"))
      (node (ref "U16") (pin "P$47") (pinfunction "VSS2_P$47") (pintype "power_in"))
      (node (ref "U16") (pin "P$63") (pinfunction "VSS3_P$63") (pintype "power_in"))
      (node (ref "U17") (pin "1") (pinfunction "GND_1") (pintype "power_in"))
      (node (ref "U2") (pin "3") (pinfunction "GND_3") (pintype "power_in"))
      (node (ref "U27") (pin "2") (pinfunction "GND_2") (pintype "power_in"))
      (node (ref "U27") (pin "8") (pinfunction "S_8") (pintype "input"))
      (node (ref "U3") (pin "4") (pinfunction "1_4") (pintype "input"))
      (node (ref "U3") (pin "5") (pinfunction "2_5") (pintype "input"))
      (node (ref "U3") (pin "9") (pinfunction "GND_9") (pintype "power_in"))
      (node (ref "U4") (pin "3") (pinfunction "GND_3") (pintype "power_in"))
      (node (ref "U5") (pin "5") (pinfunction "GND_5") (pintype "power_in"))
      (node (ref "U6") (pin "3") (pinfunction "GND_3") (pintype "power_in"))
      (node (ref "U7") (pin "3") (pinfunction "GND_3") (pintype "power_in"))
      (node (ref "U8") (pin "3") (pinfunction "GND_3") (pintype "power_in"))
      (node (ref "U9") (pin "3") (pinfunction "GND_3") (pintype "power_in"))
      (node (ref "X1") (pin "2") (pinfunction "2-CASE_2") (pintype "bidirectional"))
      (node (ref "X1") (pin "4") (pinfunction "4-CASE_4") (pintype "bidirectional"))
    )
    (net (code "28") (name "INERTIA") (class "Default")
      (node (ref "D3") (pin "2") (pinfunction "C_2") (pintype "passive"))
      (node (ref "INERTIA") (pin "1") (pinfunction "1_1") (pintype "passive"))
      (node (ref "J2") (pin "6") (pinfunction "6_6") (pintype "passive"))
      (node (ref "R3") (pin "1") (pinfunction "1_1") (pintype "passive"))
    )
    (net (code "29") (name "INERTIA_READ") (class "Default")
      (node (ref "R3") (pin "2") (pinfunction "2_2") (pintype "passive"))
      (node (ref "R8") (pin "1") (pinfunction "1_1") (pintype "passive"))
      (node (ref "U16") (pin "P$59") (pinfunction "PB7_P$59") (pintype "bidirectional"))
    )
    (net (code "30") (name "LEFT_SHIFTER") (class "Default")
      (node (ref "J3") (pin "1") (pinfunction "1_1") (pintype "passive"))
      (node (ref "U16") (pin "P$43") (pinfunction "PA10_P$43") (pintype "bidirectional"))
    )
    (net (code "31") (name "MCU_BOOT_0") (class "Default")
      (node (ref "R16") (pin "2") (pinfunction "2_2") (pintype "passive"))
      (node (ref "S2") (pin "COM") (pinfunction "COM_COM") (pintype "bidirectional"))
      (node (ref "U16") (pin "P$60") (pinfunction "BOOT0_P$60") (pintype "input"))
    )
    (net (code "32") (name "MCU_CAN_1_RX") (class "Default")
      (node (ref "U16") (pin "P$61") (pinfunction "PB8_P$61") (pintype "bidirectional"))
      (node (ref "U27") (pin "4") (pinfunction "RXD_4") (pintype "output"))
    )
    (net (code "33") (name "MCU_CAN_1_TX") (class "Default")
      (node (ref "U16") (pin "P$62") (pinfunction "PB9_P$62") (pintype "bidirectional"))
      (node (ref "U27") (pin "1") (pinfunction "TXD_1") (pintype "input"))
    )
    (net (code "34") (name "MCU_LED") (class "Default")
      (node (ref "MCU_LED") (pin "2") (pinfunction "A_2") (pintype "passive"))
      (node (ref "U16") (pin "P$17") (pinfunction "PA3_P$17") (pintype "bidirectional"))
    )
    (net (code "35") (name "MCU_NEOPIXEL") (class "Default")
      (node (ref "NEOPIXELS") (pin "1") (pinfunction "1_1") (pintype "passive"))
      (node (ref "U$6") (pin "2") (pinfunction "A1_2") (pintype "bidirectional"))
      (node (ref "U16") (pin "P$3") (pinfunction "PC14-OSC32_IN_P$3") (pintype "bidirectional"))
    )
    (net (code "36") (name "MCU_NRST") (class "Default")
      (node (ref "C14") (pin "1") (pinfunction "1_1") (pintype "passive"))
      (node (ref "R7") (pin "1") (pinfunction "1_1") (pintype "passive"))
      (node (ref "S1") (pin "1") (pinfunction "P_1") (pintype "passive"))
      (node (ref "S1") (pin "2") (pinfunction "P_2") (pintype "passive"))
      (node (ref "U16") (pin "P$7") (pinfunction "NRST_P$7") (pintype "bidirectional"))
    )
    (net (code "37") (name "MCU_OSC_IN") (class "Default")
      (node (ref "C1") (pin "1") (pinfunction "1_1") (pintype "passive"))
      (node (ref "U16") (pin "P$5") (pinfunction "PH0-OSC_IN_P$5") (pintype "bidirectional"))
      (node (ref "X1") (pin "1") (pinfunction "1-XTAL_1") (pintype "bidirectional"))
    )
    (net (code "38") (name "MCU_OSC_OUT") (class "Default")
      (node (ref "R15") (pin "2") (pinfunction "2_2") (pintype "passive"))
      (node (ref "U16") (pin "P$6") (pinfunction "PH1-OSC_OUT_P$6") (pintype "bidirectional"))
    )
    (net (code "39") (name "MCU_SPI1_MISO") (class "Default")
      (node (ref "U16") (pin "P$22") (pinfunction "PA6_P$22") (pintype "bidirectional"))
    )
    (net (code "40") (name "MCU_SPI1_MOSI") (class "Default")
      (node (ref "J5") (pin "4") (pinfunction "2_4") (pintype "passive"))
      (node (ref "SPI1_MOSI") (pin "1") (pinfunction "1_1") (pintype "passive"))
      (node (ref "U16") (pin "P$23") (pinfunction "PA7_P$23") (pintype "bidirectional"))
    )
    (net (code "41") (name "MCU_SPI1_SCK") (class "Default")
      (node (ref "J5") (pin "3") (pinfunction "1_3") (pintype "passive"))
      (node (ref "SPI1_SCK") (pin "1") (pinfunction "1_1") (pintype "passive"))
      (node (ref "U16") (pin "P$21") (pinfunction "PA5_P$21") (pintype "bidirectional"))
    )
    (net (code "42") (name "MCU_SPI2_MISO") (class "Default")
      (node (ref "U16") (pin "P$10") (pinfunction "PC2_P$10") (pintype "bidirectional"))
      (node (ref "U3") (pin "3") (pinfunction "SDO_3") (pintype "output"))
    )
    (net (code "43") (name "MCU_SPI2_MOSI") (class "Default")
      (node (ref "U16") (pin "P$9") (pinfunction "PC1_P$9") (pintype "bidirectional"))
      (node (ref "U3") (pin "2") (pinfunction "SDI_2") (pintype "input"))
    )
    (net (code "44") (name "MCU_SPI2_SCK") (class "Default")
      (node (ref "U16") (pin "P$29") (pinfunction "PB10_P$29") (pintype "bidirectional"))
      (node (ref "U3") (pin "1") (pinfunction "CLK_1") (pintype "input"))
    )
    (net (code "45") (name "MCU_SPI3_MISO") (class "Default")
      (node (ref "U16") (pin "P$52") (pinfunction "PC11_P$52") (pintype "bidirectional"))
    )
    (net (code "46") (name "MCU_SPI3_MOSI") (class "Default")
      (node (ref "J10") (pin "4") (pinfunction "2_4") (pintype "passive"))
      (node (ref "SPI3_MOSI") (pin "1") (pinfunction "1_1") (pintype "passive"))
      (node (ref "U16") (pin "P$26") (pinfunction "PB0_P$26") (pintype "bidirectional"))
    )
    (net (code "47") (name "MCU_SPI3_SCK") (class "Default")
      (node (ref "J10") (pin "3") (pinfunction "1_3") (pintype "passive"))
      (node (ref "SPI3_SCK") (pin "1") (pinfunction "1_1") (pintype "passive"))
      (node (ref "U16") (pin "P$51") (pinfunction "PC10_P$51") (pintype "bidirectional"))
    )
    (net (code "48") (name "MCU_SWCLK") (class "Default")
      (node (ref "U16") (pin "P$49") (pinfunction "PA14_P$49") (pintype "bidirectional"))
    )
    (net (code "49") (name "MCU_SWDIO") (class "Default")
      (node (ref "U16") (pin "P$46") (pinfunction "PA13_P$46") (pintype "bidirectional"))
    )
    (net (code "50") (name "MCU_SWO") (class "Default")
      (node (ref "U16") (pin "P$55") (pinfunction "PB3_P$55") (pintype "bidirectional"))
    )
    (net (code "51") (name "MCU_USB_N") (class "Default")
      (node (ref "D1") (pin "3") (pinfunction "I/O2-IN_3") (pintype "bidirectional"))
      (node (ref "U16") (pin "P$44") (pinfunction "PA11_P$44") (pintype "bidirectional"))
    )
    (net (code "52") (name "MCU_USB_P") (class "Default")
      (node (ref "D1") (pin "1") (pinfunction "I/O1-IN_1") (pintype "bidirectional"))
      (node (ref "U16") (pin "P$45") (pinfunction "PA12_P$45") (pintype "bidirectional"))
    )
    (net (code "53") (name "Net-(3V3-C)") (class "Default")
      (node (ref "3V3") (pin "1") (pinfunction "C_1") (pintype "passive"))
      (node (ref "R6") (pin "2") (pinfunction "2_2") (pintype "passive"))
    )
    (net (code "54") (name "Net-(5V-C)") (class "Default")
      (node (ref "5V") (pin "1") (pinfunction "C_1") (pintype "passive"))
      (node (ref "R21") (pin "2") (pinfunction "2_2") (pintype "passive"))
    )
    (net (code "55") (name "Net-(12V-C)") (class "Default")
      (node (ref "12V") (pin "1") (pinfunction "C_1") (pintype "passive"))
      (node (ref "R2") (pin "2") (pinfunction "2_2") (pintype "passive"))
    )
    (net (code "56") (name "Net-(24V-C)") (class "Default")
      (node (ref "24V") (pin "1") (pinfunction "C_1") (pintype "passive"))
      (node (ref "R83") (pin "2") (pinfunction "2_2") (pintype "passive"))
    )
    (net (code "57") (name "Net-(C25-Pad2)") (class "Default")
      (node (ref "C25") (pin "2") (pinfunction "2_2") (pintype "passive"))
      (node (ref "R36") (pin "1") (pinfunction "1_1") (pintype "passive"))
      (node (ref "R60") (pin "1") (pinfunction "1_1") (pintype "passive"))
    )
    (net (code "58") (name "Net-(D101-A)") (class "Default")
      (node (ref "D101") (pin "7") (pinfunction "A_7") (pintype "input"))
      (node (ref "RN2") (pin "5") (pinfunction "2_5") (pintype "passive"))
    )
    (net (code "59") (name "Net-(D101-B)") (class "Default")
      (node (ref "D101") (pin "6") (pinfunction "B_6") (pintype "input"))
      (node (ref "RN2") (pin "6") (pinfunction "2_6") (pintype "passive"))
    )
    (net (code "60") (name "Net-(D101-C)") (class "Default")
      (node (ref "D101") (pin "4") (pinfunction "C_4") (pintype "input"))
      (node (ref "RN2") (pin "7") (pinfunction "2_7") (pintype "passive"))
    )
    (net (code "61") (name "Net-(D101-D)") (class "Default")
      (node (ref "D101") (pin "2") (pinfunction "D_2") (pintype "input"))
      (node (ref "RN2") (pin "8") (pinfunction "2_8") (pintype "passive"))
    )
    (net (code "62") (name "Net-(D101-E)") (class "Default")
      (node (ref "D101") (pin "1") (pinfunction "E_1") (pintype "input"))
      (node (ref "RN4") (pin "6") (pinfunction "2_6") (pintype "passive"))
    )
    (net (code "63") (name "Net-(D101-F)") (class "Default")
      (node (ref "D101") (pin "9") (pinfunction "F_9") (pintype "input"))
      (node (ref "RN4") (pin "7") (pinfunction "2_7") (pintype "passive"))
    )
    (net (code "64") (name "Net-(D101-G)") (class "Default")
      (node (ref "D101") (pin "10") (pinfunction "G_10") (pintype "input"))
      (node (ref "RN4") (pin "8") (pinfunction "2_8") (pintype "passive"))
    )
    (net (code "65") (name "Net-(J7-Pad3)") (class "Default")
      (node (ref "J7") (pin "3") (pinfunction "3_3") (pintype "passive"))
      (node (ref "J7") (pin "4") (pinfunction "4_4") (pintype "passive"))
      (node (ref "R20") (pin "2") (pinfunction "2_2") (pintype "passive"))
    )
    (net (code "66") (name "Net-(J8-CC1)") (class "Default")
      (node (ref "J8") (pin "P$4") (pinfunction "CC1_P$4") (pintype "passive"))
      (node (ref "R17") (pin "2") (pinfunction "2_2") (pintype "passive"))
    )
    (net (code "67") (name "Net-(J8-CC2)") (class "Default")
      (node (ref "J8") (pin "P$10") (pinfunction "CC2_P$10") (pintype "passive"))
      (node (ref "R18") (pin "2") (pinfunction "2_2") (pintype "passive"))
    )
    (net (code "68") (name "Net-(J9-Pad3)") (class "Default")
      (node (ref "J9") (pin "3") (pinfunction "3_3") (pintype "passive"))
      (node (ref "J9") (pin "4") (pinfunction "4_4") (pintype "passive"))
      (node (ref "R19") (pin "2") (pinfunction "2_2") (pintype "passive"))
    )
    (net (code "69") (name "Net-(LS100-FEEDBACK)") (class "Default")
      (node (ref "LS100") (pin "F") (pinfunction "FEEDBACK_F") (pintype "bidirectional"))
      (node (ref "R9") (pin "2") (pinfunction "2_2") (pintype "passive"))
    )
    (net (code "70") (name "Net-(LS100-GND)") (class "Default")
      (node (ref "LS100") (pin "G") (pinfunction "GND_G") (pintype "power_in"))
      (node (ref "R13") (pin "1") (pinfunction "1_1") (pintype "passive"))
      (node (ref "U5") (pin "6") (pinfunction "HORNB_6") (pintype "output"))
    )
    (net (code "71") (name "Net-(LS100-MAIN)") (class "Default")
      (node (ref "C17") (pin "1") (pinfunction "1_1") (pintype "passive"))
      (node (ref "LS100") (pin "M") (pinfunction "MAIN_M") (pintype "power_in"))
      (node (ref "U5") (pin "7") (pinfunction "HORNS_7") (pintype "output"))
    )
    (net (code "72") (name "Net-(MCU_LED-C)") (class "Default")
      (node (ref "MCU_LED") (pin "1") (pinfunction "C_1") (pintype "passive"))
      (node (ref "R1") (pin "2") (pinfunction "2_2") (pintype "passive"))
    )
    (net (code "73") (name "Net-(RN2B-1)") (class "Default")
      (node (ref "RN2") (pin "2") (pinfunction "1_2") (pintype "passive"))
      (node (ref "U3") (pin "14") (pinfunction "GPA2_14") (pintype "bidirectional"))
    )
    (net (code "74") (name "Net-(RN2C-1)") (class "Default")
      (node (ref "RN2") (pin "3") (pinfunction "1_3") (pintype "passive"))
      (node (ref "U3") (pin "13") (pinfunction "GPA1_13") (pintype "bidirectional"))
    )
    (net (code "75") (name "Net-(RN2D-1)") (class "Default")
      (node (ref "RN2") (pin "4") (pinfunction "1_4") (pintype "passive"))
      (node (ref "U3") (pin "12") (pinfunction "GPA0_12") (pintype "bidirectional"))
    )
    (net (code "76") (name "Net-(RN4B-1)") (class "Default")
      (node (ref "RN4") (pin "2") (pinfunction "1_2") (pintype "passive"))
      (node (ref "U3") (pin "17") (pinfunction "GPA5_17") (pintype "bidirectional"))
    )
    (net (code "77") (name "Net-(RN4C-1)") (class "Default")
      (node (ref "RN4") (pin "3") (pinfunction "1_3") (pintype "passive"))
      (node (ref "U3") (pin "16") (pinfunction "GPA4_16") (pintype "bidirectional"))
    )
    (net (code "78") (name "Net-(U$6-B1)") (class "Default")
      (node (ref "U$6") (pin "7") (pinfunction "B1_7") (pintype "bidirectional"))
      (node (ref "U1") (pin "4") (pinfunction "DIN_4") (pintype "input"))
    )
    (net (code "79") (name "Net-(U1-DOUT)") (class "Default")
      (node (ref "U1") (pin "2") (pinfunction "DOUT_2") (pintype "output"))
      (node (ref "U2") (pin "4") (pinfunction "DIN_4") (pintype "input"))
    )
    (net (code "80") (name "Net-(U2-DOUT)") (class "Default")
      (node (ref "U2") (pin "2") (pinfunction "DOUT_2") (pintype "output"))
      (node (ref "U4") (pin "4") (pinfunction "DIN_4") (pintype "input"))
    )
    (net (code "81") (name "Net-(U3-GPA3)") (class "Default")
      (node (ref "RN2") (pin "1") (pinfunction "1_1") (pintype "passive"))
      (node (ref "U3") (pin "15") (pinfunction "GPA3_15") (pintype "bidirectional"))
    )
    (net (code "82") (name "Net-(U3-GPA6)") (class "Default")
      (node (ref "RN4") (pin "1") (pinfunction "1_1") (pintype "passive"))
      (node (ref "U3") (pin "18") (pinfunction "GPA6_18") (pintype "bidirectional"))
    )
    (net (code "83") (name "Net-(U4-DOUT)") (class "Default")
      (node (ref "U4") (pin "2") (pinfunction "DOUT_2") (pintype "output"))
      (node (ref "U6") (pin "4") (pinfunction "DIN_4") (pintype "input"))
    )
    (net (code "84") (name "Net-(U5-FEED)") (class "Default")
      (node (ref "C17") (pin "2") (pinfunction "2_2") (pintype "passive"))
      (node (ref "R13") (pin "2") (pinfunction "2_2") (pintype "passive"))
      (node (ref "R9") (pin "1") (pinfunction "1_1") (pintype "passive"))
      (node (ref "U5") (pin "4") (pinfunction "FEED_4") (pintype "input"))
    )
    (net (code "85") (name "Net-(U6-DOUT)") (class "Default")
      (node (ref "U6") (pin "2") (pinfunction "DOUT_2") (pintype "output"))
      (node (ref "U7") (pin "4") (pinfunction "DIN_4") (pintype "input"))
    )
    (net (code "86") (name "Net-(U7-DOUT)") (class "Default")
      (node (ref "U7") (pin "2") (pinfunction "DOUT_2") (pintype "output"))
      (node (ref "U8") (pin "4") (pinfunction "DIN_4") (pintype "input"))
    )
    (net (code "87") (name "Net-(U8-DOUT)") (class "Default")
      (node (ref "U8") (pin "2") (pinfunction "DOUT_2") (pintype "output"))
      (node (ref "U9") (pin "4") (pinfunction "DIN_4") (pintype "input"))
    )
    (net (code "88") (name "Net-(U10-DIN)") (class "Default")
      (node (ref "U10") (pin "4") (pinfunction "DIN_4") (pintype "input"))
      (node (ref "U9") (pin "2") (pinfunction "DOUT_2") (pintype "output"))
    )
    (net (code "89") (name "Net-(U10-DOUT)") (class "Default")
      (node (ref "U10") (pin "2") (pinfunction "DOUT_2") (pintype "output"))
      (node (ref "U12") (pin "4") (pinfunction "DIN_4") (pintype "input"))
    )
    (net (code "90") (name "Net-(U12-DOUT)") (class "Default")
      (node (ref "U12") (pin "2") (pinfunction "DOUT_2") (pintype "output"))
      (node (ref "U13") (pin "4") (pinfunction "DIN_4") (pintype "input"))
    )
    (net (code "91") (name "Net-(U13-DOUT)") (class "Default")
      (node (ref "U13") (pin "2") (pinfunction "DOUT_2") (pintype "output"))
      (node (ref "U14") (pin "4") (pinfunction "DIN_4") (pintype "input"))
    )
    (net (code "92") (name "Net-(U14-DOUT)") (class "Default")
      (node (ref "U14") (pin "2") (pinfunction "DOUT_2") (pintype "output"))
      (node (ref "U15") (pin "4") (pinfunction "DIN_4") (pintype "input"))
    )
    (net (code "93") (name "RIGHT_SHIFTER") (class "Default")
      (node (ref "J3") (pin "2") (pinfunction "2_2") (pintype "passive"))
      (node (ref "U16") (pin "P$42") (pinfunction "PA9_P$42") (pintype "bidirectional"))
    )
    (net (code "94") (name "SHARP_CS") (class "Default")
      (node (ref "J10") (pin "5") (pinfunction "3_5") (pintype "passive"))
      (node (ref "J5") (pin "5") (pinfunction "3_5") (pintype "passive"))
      (node (ref "U16") (pin "P$24") (pinfunction "PC4_P$24") (pintype "bidirectional"))
    )
    (net (code "95") (name "SHARP_EXTMODE") (class "Default")
      (node (ref "J10") (pin "10") (pinfunction "8_10") (pintype "passive"))
      (node (ref "J5") (pin "10") (pinfunction "8_10") (pintype "passive"))
      (node (ref "U16") (pin "P$27") (pinfunction "PB1_P$27") (pintype "bidirectional"))
    )
    (net (code "96") (name "SHARP_VCOMM") (class "Default")
      (node (ref "J10") (pin "6") (pinfunction "4_6") (pintype "passive"))
      (node (ref "J5") (pin "6") (pinfunction "4_6") (pintype "passive"))
      (node (ref "U16") (pin "P$25") (pinfunction "PC5_P$25") (pintype "bidirectional"))
    )
    (net (code "97") (name "USB_N") (class "Default")
      (node (ref "D1") (pin "4") (pinfunction "I/O2-OUT_4") (pintype "bidirectional"))
      (node (ref "J8") (pin "P$5") (pinfunction "DN2_P$5") (pintype "bidirectional"))
      (node (ref "J8") (pin "P$7") (pinfunction "DN1_P$7") (pintype "bidirectional"))
    )
    (net (code "98") (name "USB_P") (class "Default")
      (node (ref "D1") (pin "6") (pinfunction "I/O1-OUT_6") (pintype "bidirectional"))
      (node (ref "J8") (pin "P$6") (pinfunction "DP1_P$6") (pintype "bidirectional"))
      (node (ref "J8") (pin "P$8") (pinfunction "DP2_P$8") (pintype "bidirectional"))
    )
    (net (code "99") (name "VCAP_1") (class "Default")
      (node (ref "C3") (pin "1") (pinfunction "1_1") (pintype "passive"))
      (node (ref "U16") (pin "P$30") (pinfunction "VCAP_1_P$30") (pintype "power_in"))
    )
    (net (code "100") (name "XTAL_IN") (class "Default")
      (node (ref "C2") (pin "1") (pinfunction "1_1") (pintype "passive"))
      (node (ref "R15") (pin "1") (pinfunction "1_1") (pintype "passive"))
      (node (ref "X1") (pin "3") (pinfunction "3-XTAL_3") (pintype "bidirectional"))
    )
    (net (code "101") (name "unconnected-(J2-Pad7)") (class "Default")
      (node (ref "J2") (pin "7") (pinfunction "7_7") (pintype "passive"))
    )
    (net (code "102") (name "unconnected-(J3-Pad3)") (class "Default")
      (node (ref "J3") (pin "3") (pinfunction "3_3") (pintype "passive"))
    )
    (net (code "103") (name "unconnected-(J8-SBU1-PadP$9)") (class "Default")
      (node (ref "J8") (pin "P$9") (pinfunction "SBU1_P$9") (pintype "bidirectional"))
    )
    (net (code "104") (name "unconnected-(J8-SBU2-PadP$3)") (class "Default")
      (node (ref "J8") (pin "P$3") (pinfunction "SBU2_P$3") (pintype "bidirectional"))
    )
    (net (code "105") (name "unconnected-(J11-Pad1)") (class "Default")
      (node (ref "J11") (pin "1") (pinfunction "1_1") (pintype "passive"))
    )
    (net (code "106") (name "unconnected-(U$6-A2-Pad3)") (class "Default")
      (node (ref "U$6") (pin "3") (pinfunction "A2_3") (pintype "bidirectional"))
    )
    (net (code "107") (name "unconnected-(U$6-B2-Pad6)") (class "Default")
      (node (ref "U$6") (pin "6") (pinfunction "B2_6") (pintype "bidirectional"))
    )
    (net (code "108") (name "unconnected-(U3-GPA7-Pad19)") (class "Default")
      (node (ref "U3") (pin "19") (pinfunction "GPA7_19") (pintype "bidirectional"))
    )
    (net (code "109") (name "unconnected-(U3-INT-Pad8)") (class "Default")
      (node (ref "U3") (pin "8") (pinfunction "INT_8") (pintype "output"))
    )
    (net (code "110") (name "unconnected-(U15-DOUT-Pad2)") (class "Default")
      (node (ref "U15") (pin "2") (pinfunction "DOUT_2") (pintype "output"))
    )
    (net (code "111") (name "unconnected-(U16-PA0-PadP$14)") (class "Default")
      (node (ref "U16") (pin "P$14") (pinfunction "PA0_P$14") (pintype "bidirectional"))
    )
    (net (code "112") (name "unconnected-(U16-PA1-PadP$15)") (class "Default")
      (node (ref "U16") (pin "P$15") (pinfunction "PA1_P$15") (pintype "bidirectional"))
    )
    (net (code "113") (name "unconnected-(U16-PA2-PadP$16)") (class "Default")
      (node (ref "U16") (pin "P$16") (pinfunction "PA2_P$16") (pintype "bidirectional"))
    )
    (net (code "114") (name "unconnected-(U16-PA4-PadP$20)") (class "Default")
      (node (ref "U16") (pin "P$20") (pinfunction "PA4_P$20") (pintype "bidirectional"))
    )
    (net (code "115") (name "unconnected-(U16-PB2-PadP$28)") (class "Default")
      (node (ref "U16") (pin "P$28") (pinfunction "PB2_P$28") (pintype "bidirectional"))
    )
    (net (code "116") (name "unconnected-(U16-PB4-PadP$56)") (class "Default")
      (node (ref "U16") (pin "P$56") (pinfunction "PB4_P$56") (pintype "bidirectional"))
    )
    (net (code "117") (name "unconnected-(U16-PC0-PadP$8)") (class "Default")
      (node (ref "U16") (pin "P$8") (pinfunction "PC0_P$8") (pintype "bidirectional"))
    )
    (net (code "118") (name "unconnected-(U16-PC3-PadP$11)") (class "Default")
      (node (ref "U16") (pin "P$11") (pinfunction "PC3_P$11") (pintype "bidirectional"))
    )
    (net (code "119") (name "unconnected-(U16-PC15-OSC32_OUT-PadP$4)") (class "Default")
      (node (ref "U16") (pin "P$4") (pinfunction "PC15-OSC32_OUT_P$4") (pintype "bidirectional"))
    )
  )
)
